# Dx32_V1_0.net
KiCad netlist of a schematic drawn in EAGLE
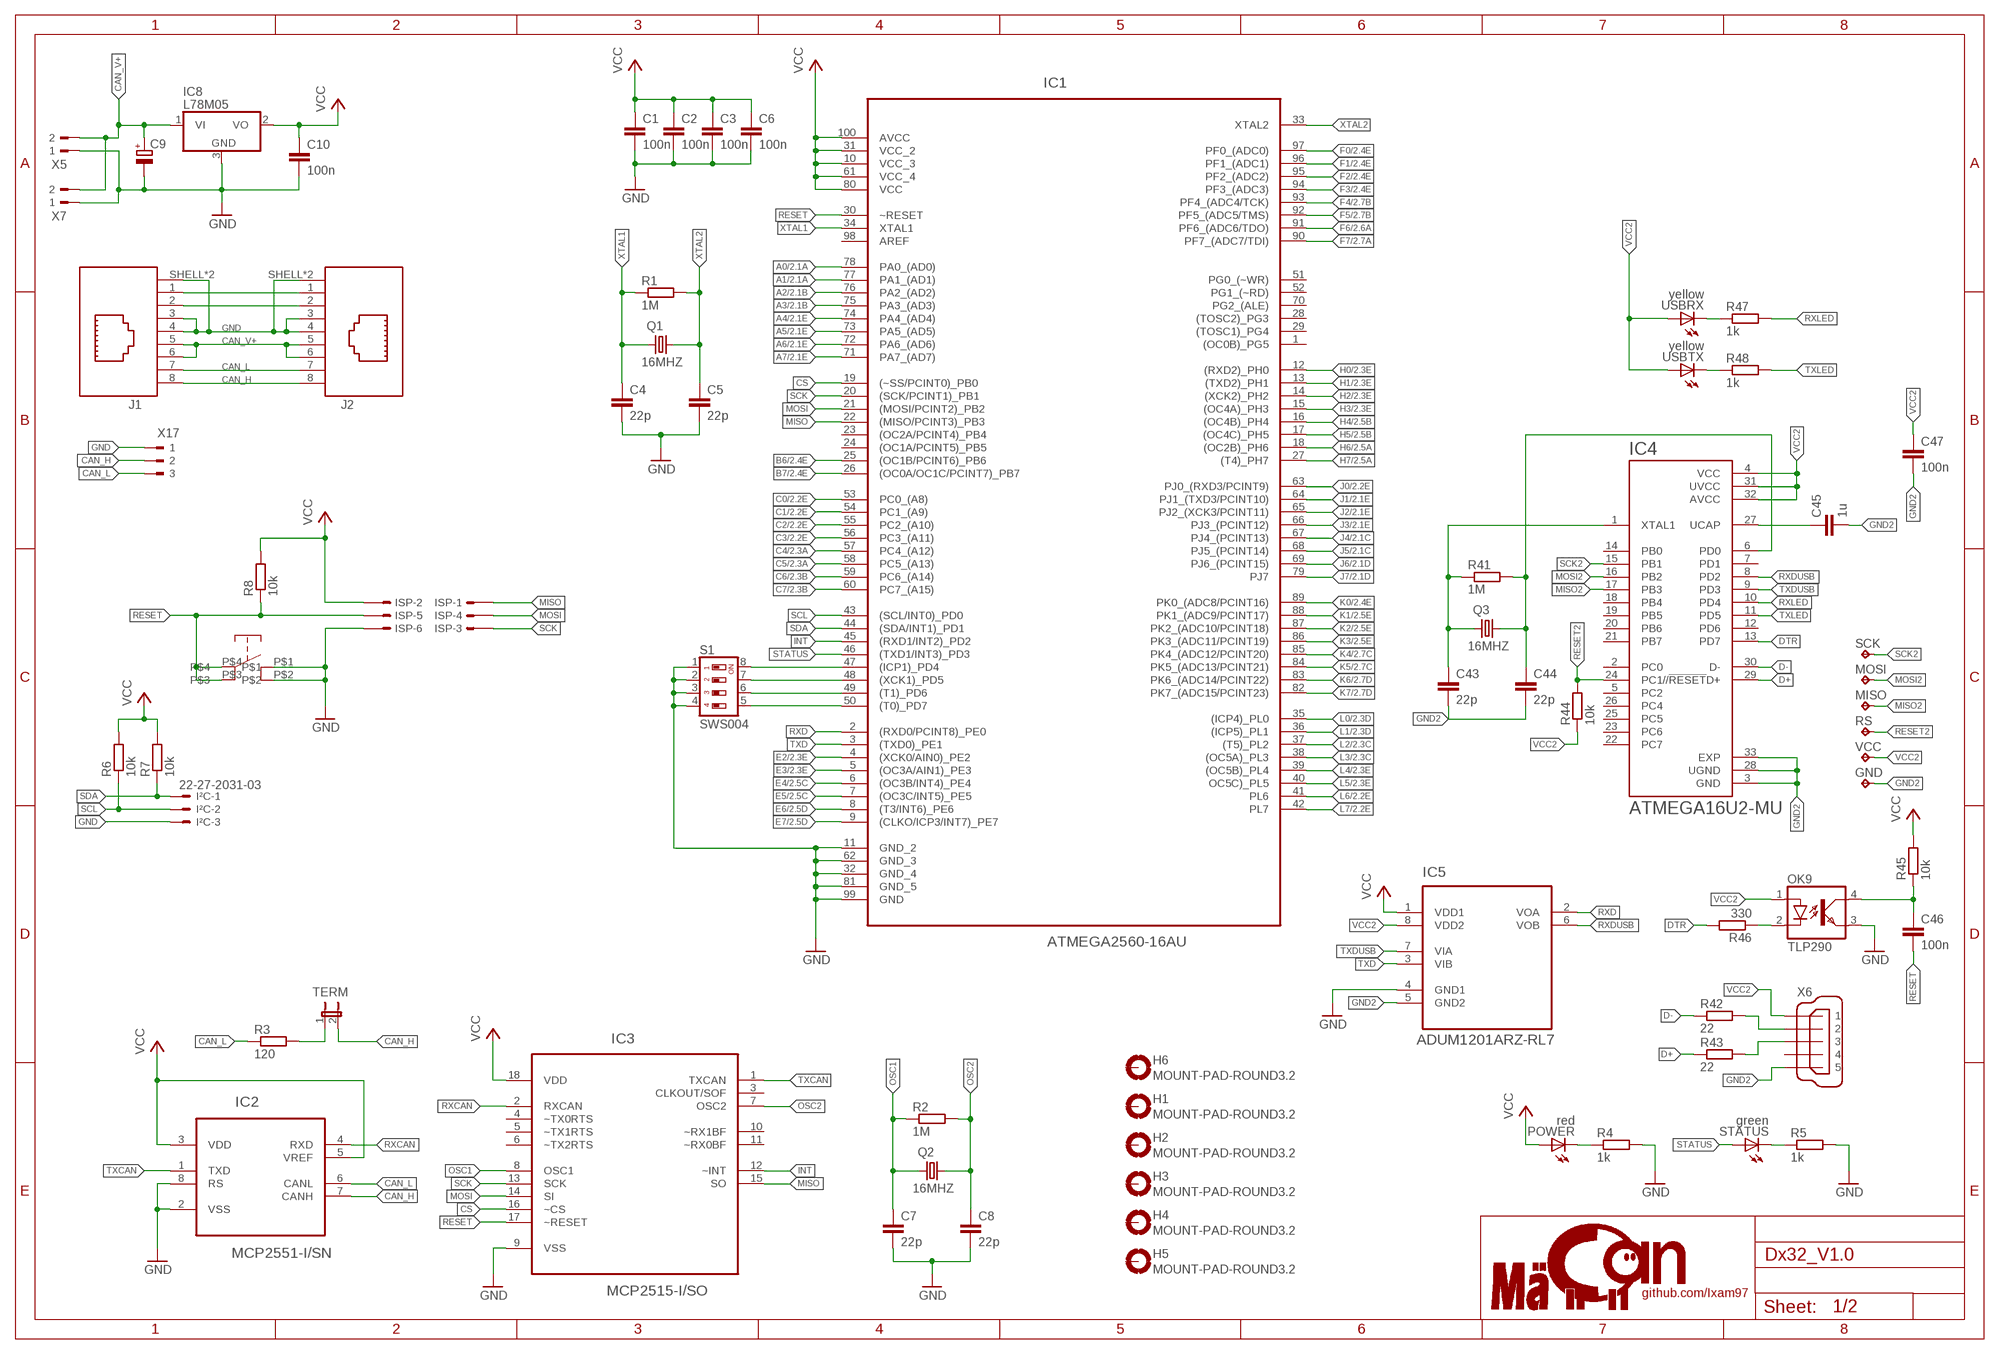
[diagram p0: schematic, sheet 1]
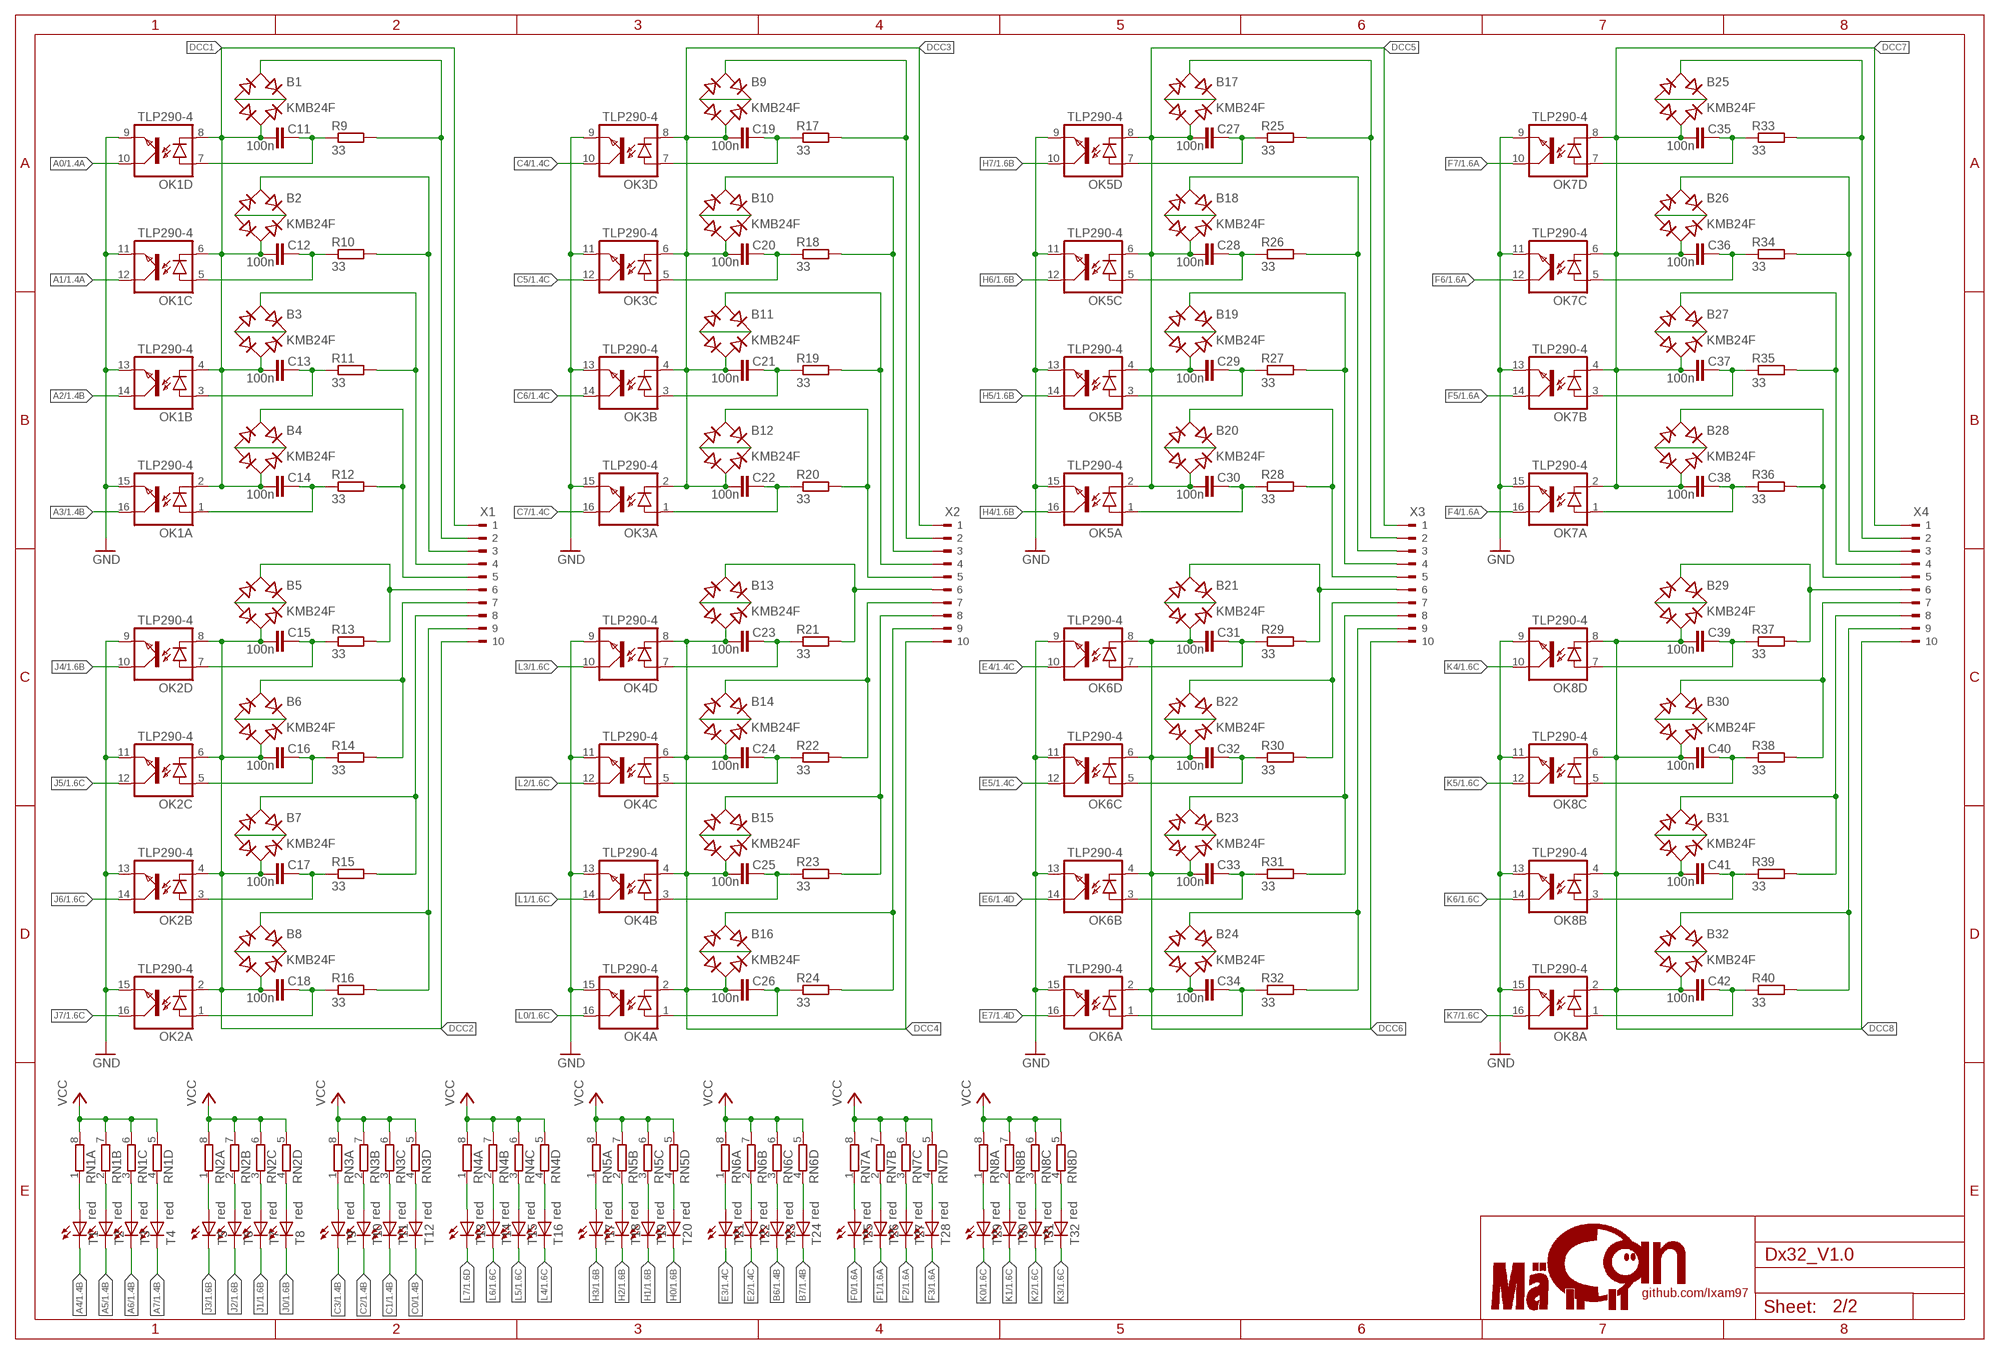
[diagram p1: schematic, sheet 2]

(export (version "E")
  (design (tool "Eeschema 10.0.6"))
  (components
    (comp (ref "C1")
      (value "100n")
      (footprint "eagle-import:C0402")
      (libsource (lib "eagle-import") (part "C-EUC0402"))
    )
    (comp (ref "C2")
      (value "100n")
      (footprint "eagle-import:C0402")
      (libsource (lib "eagle-import") (part "C-EUC0402"))
    )
    (comp (ref "C3")
      (value "100n")
      (footprint "eagle-import:C0402")
      (libsource (lib "eagle-import") (part "C-EUC0402"))
    )
    (comp (ref "C4")
      (value "22p")
      (footprint "eagle-import:C0402")
      (libsource (lib "eagle-import") (part "C-EUC0402"))
    )
    (comp (ref "C5")
      (value "22p")
      (footprint "eagle-import:C0402")
      (libsource (lib "eagle-import") (part "C-EUC0402"))
    )
    (comp (ref "C6")
      (value "100n")
      (footprint "eagle-import:C0402")
      (libsource (lib "eagle-import") (part "C-EUC0402"))
    )
    (comp (ref "C7")
      (value "22p")
      (footprint "eagle-import:C0402")
      (libsource (lib "eagle-import") (part "C-EUC0402"))
    )
    (comp (ref "C8")
      (value "22p")
      (footprint "eagle-import:C0402")
      (libsource (lib "eagle-import") (part "C-EUC0402"))
    )
    (comp (ref "C9")
      (value "CPOL-EUCT3216")
      (footprint "eagle-import:CT3216")
      (libsource (lib "eagle-import") (part "CPOL-EUCT3216"))
    )
    (comp (ref "C10")
      (value "100n")
      (footprint "eagle-import:C0402")
      (libsource (lib "eagle-import") (part "C-EUC0402"))
    )
    (comp (ref "C43")
      (value "22p")
      (footprint "eagle-import:C0402")
      (libsource (lib "eagle-import") (part "C-EUC0402"))
    )
    (comp (ref "C44")
      (value "22p")
      (footprint "eagle-import:C0402")
      (libsource (lib "eagle-import") (part "C-EUC0402"))
    )
    (comp (ref "C45")
      (value "1u")
      (footprint "eagle-import:C0402")
      (libsource (lib "eagle-import") (part "C-EUC0402"))
    )
    (comp (ref "C46")
      (value "100n")
      (footprint "eagle-import:C0402")
      (libsource (lib "eagle-import") (part "C-EUC0402"))
    )
    (comp (ref "C47")
      (value "100n")
      (footprint "eagle-import:C0402")
      (libsource (lib "eagle-import") (part "C-EUC0402"))
    )
    (comp (ref "GND")
      (value "TPB1,27")
      (footprint "eagle-import:B1,27")
      (libsource (lib "eagle-import") (part "TPB1,27"))
    )
    (comp (ref "H1")
      (value "MOUNT-PAD-ROUND3.2")
      (footprint "eagle-import:3,2-PAD")
      (libsource (lib "eagle-import") (part "MOUNT-PAD-ROUND3.2"))
    )
    (comp (ref "H2")
      (value "MOUNT-PAD-ROUND3.2")
      (footprint "eagle-import:3,2-PAD")
      (libsource (lib "eagle-import") (part "MOUNT-PAD-ROUND3.2"))
    )
    (comp (ref "H3")
      (value "MOUNT-PAD-ROUND3.2")
      (footprint "eagle-import:3,2-PAD")
      (libsource (lib "eagle-import") (part "MOUNT-PAD-ROUND3.2"))
    )
    (comp (ref "H4")
      (value "MOUNT-PAD-ROUND3.2")
      (footprint "eagle-import:3,2-PAD")
      (libsource (lib "eagle-import") (part "MOUNT-PAD-ROUND3.2"))
    )
    (comp (ref "H5")
      (value "MOUNT-PAD-ROUND3.2")
      (footprint "eagle-import:3,2-PAD")
      (libsource (lib "eagle-import") (part "MOUNT-PAD-ROUND3.2"))
    )
    (comp (ref "H6")
      (value "MOUNT-PAD-ROUND3.2")
      (footprint "eagle-import:3,2-PAD")
      (libsource (lib "eagle-import") (part "MOUNT-PAD-ROUND3.2"))
    )
    (comp (ref "IC1")
      (value "ATMEGA2560-16AU")
      (footprint "eagle-import:QFP50P1600X1600X120-100N")
      (fields (field (name "MF") "Microchip"))
      (libsource (lib "eagle-import") (part "ATMEGA2560-16AU"))
    )
    (comp (ref "IC2")
      (value "MCP2551-I/SN")
      (footprint "eagle-import:SOIC127P600X175-8N")
      (libsource (lib "eagle-import") (part "MCP2551-I/SN"))
    )
    (comp (ref "IC3")
      (value "MCP2515-I/SO")
      (footprint "eagle-import:SOIC127P1034X264-18N")
      (libsource (lib "eagle-import") (part "MCP2515-I/SO"))
    )
    (comp (ref "IC4")
      (value "ATMEGA16U2-MU")
      (footprint "eagle-import:QFN50P500X500X100-33N")
      (fields (field (name "MF") "Microchip"))
      (libsource (lib "eagle-import") (part "ATMEGA16U2-MU"))
    )
    (comp (ref "IC5")
      (value "ADUM1201ARZ-RL7")
      (footprint "eagle-import:SOIC127P600X175-8N")
      (fields (field (name "MF") "Analog Devices"))
      (libsource (lib "eagle-import") (part "ADUM1201ARZ-RL7"))
    )
    (comp (ref "IC8")
      (value "L78M05")
      (footprint "eagle-import:TO252")
      (fields (field (name "JLCPCB-PART") "C58069"))
      (libsource (lib "eagle-import") (part "78DT05"))
    )
    (comp (ref "ISP")
      (value "057-006-1")
      (footprint "eagle-import:057-006-1")
      (libsource (lib "eagle-import") (part "057-006-1"))
    )
    (comp (ref "I²C")
      (value "22-27-2031-03")
      (footprint "eagle-import:6410-03")
      (fields (field (name "MF") "MOLEX"))
      (libsource (lib "eagle-import") (part "22-?-0327-2031"))
    )
    (comp (ref "J1")
      (value "615008140421")
      (footprint "eagle-import:615008140421")
      (libsource (lib "eagle-import") (part "615008140421"))
    )
    (comp (ref "J2")
      (value "615008140421")
      (footprint "eagle-import:615008140421")
      (libsource (lib "eagle-import") (part "615008140421"))
    )
    (comp (ref "MISO")
      (value "TPB1,27")
      (footprint "eagle-import:B1,27")
      (libsource (lib "eagle-import") (part "TPB1,27"))
    )
    (comp (ref "MOSI")
      (value "TPB1,27")
      (footprint "eagle-import:B1,27")
      (libsource (lib "eagle-import") (part "TPB1,27"))
    )
    (comp (ref "OK9")
      (value "TLP290")
      (footprint "eagle-import:MINI-FLAT-4")
      (libsource (lib "eagle-import") (part "TLP283"))
    )
    (comp (ref "POWER")
      (value "red")
      (footprint "eagle-import:CHIP-LED0805")
      (libsource (lib "eagle-import") (part "LEDCHIP-LED0805"))
    )
    (comp (ref "Q1")
      (value "16MHZ")
      (footprint "eagle-import:3.2X2.5_KX-7")
      (libsource (lib "eagle-import") (part "KX-7"))
    )
    (comp (ref "Q2")
      (value "16MHZ")
      (footprint "eagle-import:3.2X2.5_KX-7")
      (libsource (lib "eagle-import") (part "KX-7"))
    )
    (comp (ref "Q3")
      (value "16MHZ")
      (footprint "eagle-import:3.2X2.5_KX-7")
      (libsource (lib "eagle-import") (part "KX-7"))
    )
    (comp (ref "R1")
      (value "1M")
      (footprint "eagle-import:R0402")
      (libsource (lib "eagle-import") (part "R-EU_R0402"))
    )
    (comp (ref "R2")
      (value "1M")
      (footprint "eagle-import:R0402")
      (libsource (lib "eagle-import") (part "R-EU_R0402"))
    )
    (comp (ref "R3")
      (value "120")
      (footprint "eagle-import:R0402")
      (libsource (lib "eagle-import") (part "R-EU_R0402"))
    )
    (comp (ref "R4")
      (value "1k")
      (footprint "eagle-import:R0402")
      (libsource (lib "eagle-import") (part "R-EU_R0402"))
    )
    (comp (ref "R5")
      (value "1k")
      (footprint "eagle-import:R0402")
      (libsource (lib "eagle-import") (part "R-EU_R0402"))
    )
    (comp (ref "R6")
      (value "10k")
      (footprint "eagle-import:R0402")
      (libsource (lib "eagle-import") (part "R-EU_R0402"))
    )
    (comp (ref "R7")
      (value "10k")
      (footprint "eagle-import:R0402")
      (libsource (lib "eagle-import") (part "R-EU_R0402"))
    )
    (comp (ref "R8")
      (value "10k")
      (footprint "eagle-import:R0402")
      (libsource (lib "eagle-import") (part "R-EU_R0402"))
    )
    (comp (ref "R41")
      (value "1M")
      (footprint "eagle-import:R0402")
      (libsource (lib "eagle-import") (part "R-EU_R0402"))
    )
    (comp (ref "R42")
      (value "22")
      (footprint "eagle-import:R0402")
      (libsource (lib "eagle-import") (part "R-EU_R0402"))
    )
    (comp (ref "R43")
      (value "22")
      (footprint "eagle-import:R0402")
      (libsource (lib "eagle-import") (part "R-EU_R0402"))
    )
    (comp (ref "R44")
      (value "10k")
      (footprint "eagle-import:R0402")
      (libsource (lib "eagle-import") (part "R-EU_R0402"))
    )
    (comp (ref "R45")
      (value "10k")
      (footprint "eagle-import:R0402")
      (libsource (lib "eagle-import") (part "R-EU_R0402"))
    )
    (comp (ref "R46")
      (value "330")
      (footprint "eagle-import:R0402")
      (libsource (lib "eagle-import") (part "R-EU_R0402"))
    )
    (comp (ref "R47")
      (value "1k")
      (footprint "eagle-import:R0402")
      (libsource (lib "eagle-import") (part "R-EU_R0402"))
    )
    (comp (ref "R48")
      (value "1k")
      (footprint "eagle-import:R0402")
      (libsource (lib "eagle-import") (part "R-EU_R0402"))
    )
    (comp (ref "RS")
      (value "TPB1,27")
      (footprint "eagle-import:B1,27")
      (libsource (lib "eagle-import") (part "TPB1,27"))
    )
    (comp (ref "S1")
      (value "SWS004")
      (footprint "eagle-import:SMS-004")
      (libsource (lib "eagle-import") (part "SWS004"))
    )
    (comp (ref "SCK")
      (value "TPB1,27")
      (footprint "eagle-import:B1,27")
      (libsource (lib "eagle-import") (part "TPB1,27"))
    )
    (comp (ref "STATUS")
      (value "green")
      (footprint "eagle-import:CHIP-LED0805")
      (libsource (lib "eagle-import") (part "LEDCHIP-LED0805"))
    )
    (comp (ref "TERM")
      (value "JP1E")
      (footprint "eagle-import:JP1")
      (libsource (lib "eagle-import") (part "JP1E"))
    )
    (comp (ref "U$15")
      (value "BUTTON_JLC")
      (footprint "eagle-import:BUTTON")
      (libsource (lib "eagle-import") (part "BUTTON_JLC"))
    )
    (comp (ref "USBRX")
      (value "yellow")
      (footprint "eagle-import:CHIP-LED0805")
      (libsource (lib "eagle-import") (part "LEDCHIP-LED0805"))
    )
    (comp (ref "USBTX")
      (value "yellow")
      (footprint "eagle-import:CHIP-LED0805")
      (libsource (lib "eagle-import") (part "LEDCHIP-LED0805"))
    )
    (comp (ref "VCC")
      (value "TPB1,27")
      (footprint "eagle-import:B1,27")
      (libsource (lib "eagle-import") (part "TPB1,27"))
    )
    (comp (ref "X5")
      (value "180-2")
      (footprint "eagle-import:180-2")
      (libsource (lib "eagle-import") (part "180-2"))
    )
    (comp (ref "X6")
      (value "MINI-USB_SHIELD5P2-32005-601")
      (footprint "eagle-import:32005-601")
      (libsource (lib "eagle-import") (part "MINI-USB_SHIELD5P2-32005-601"))
    )
    (comp (ref "X7")
      (value "180-2")
      (footprint "eagle-import:180-2")
      (libsource (lib "eagle-import") (part "180-2"))
    )
    (comp (ref "X17")
      (value "180-3")
      (footprint "eagle-import:180-3")
      (libsource (lib "eagle-import") (part "180-3"))
    )
    (comp (ref "B1")
      (value "KMB24F")
      (footprint "eagle-import:MBS")
      (fields (field (name "JLCPCB-PART") "C113927"))
      (libsource (lib "eagle-import") (part "BS2"))
    )
    (comp (ref "B2")
      (value "KMB24F")
      (footprint "eagle-import:MBS")
      (libsource (lib "eagle-import") (part "BS2"))
    )
    (comp (ref "B3")
      (value "KMB24F")
      (footprint "eagle-import:MBS")
      (libsource (lib "eagle-import") (part "BS2"))
    )
    (comp (ref "B4")
      (value "KMB24F")
      (footprint "eagle-import:MBS")
      (libsource (lib "eagle-import") (part "BS2"))
    )
    (comp (ref "B5")
      (value "KMB24F")
      (footprint "eagle-import:MBS")
      (libsource (lib "eagle-import") (part "BS2"))
    )
    (comp (ref "B6")
      (value "KMB24F")
      (footprint "eagle-import:MBS")
      (libsource (lib "eagle-import") (part "BS2"))
    )
    (comp (ref "B7")
      (value "KMB24F")
      (footprint "eagle-import:MBS")
      (libsource (lib "eagle-import") (part "BS2"))
    )
    (comp (ref "B8")
      (value "KMB24F")
      (footprint "eagle-import:MBS")
      (libsource (lib "eagle-import") (part "BS2"))
    )
    (comp (ref "B9")
      (value "KMB24F")
      (footprint "eagle-import:MBS")
      (libsource (lib "eagle-import") (part "BS2"))
    )
    (comp (ref "B10")
      (value "KMB24F")
      (footprint "eagle-import:MBS")
      (libsource (lib "eagle-import") (part "BS2"))
    )
    (comp (ref "B11")
      (value "KMB24F")
      (footprint "eagle-import:MBS")
      (libsource (lib "eagle-import") (part "BS2"))
    )
    (comp (ref "B12")
      (value "KMB24F")
      (footprint "eagle-import:MBS")
      (libsource (lib "eagle-import") (part "BS2"))
    )
    (comp (ref "B13")
      (value "KMB24F")
      (footprint "eagle-import:MBS")
      (libsource (lib "eagle-import") (part "BS2"))
    )
    (comp (ref "B14")
      (value "KMB24F")
      (footprint "eagle-import:MBS")
      (libsource (lib "eagle-import") (part "BS2"))
    )
    (comp (ref "B15")
      (value "KMB24F")
      (footprint "eagle-import:MBS")
      (libsource (lib "eagle-import") (part "BS2"))
    )
    (comp (ref "B16")
      (value "KMB24F")
      (footprint "eagle-import:MBS")
      (libsource (lib "eagle-import") (part "BS2"))
    )
    (comp (ref "B17")
      (value "KMB24F")
      (footprint "eagle-import:MBS")
      (libsource (lib "eagle-import") (part "BS2"))
    )
    (comp (ref "B18")
      (value "KMB24F")
      (footprint "eagle-import:MBS")
      (libsource (lib "eagle-import") (part "BS2"))
    )
    (comp (ref "B19")
      (value "KMB24F")
      (footprint "eagle-import:MBS")
      (libsource (lib "eagle-import") (part "BS2"))
    )
    (comp (ref "B20")
      (value "KMB24F")
      (footprint "eagle-import:MBS")
      (libsource (lib "eagle-import") (part "BS2"))
    )
    (comp (ref "B21")
      (value "KMB24F")
      (footprint "eagle-import:MBS")
      (libsource (lib "eagle-import") (part "BS2"))
    )
    (comp (ref "B22")
      (value "KMB24F")
      (footprint "eagle-import:MBS")
      (libsource (lib "eagle-import") (part "BS2"))
    )
    (comp (ref "B23")
      (value "KMB24F")
      (footprint "eagle-import:MBS")
      (libsource (lib "eagle-import") (part "BS2"))
    )
    (comp (ref "B24")
      (value "KMB24F")
      (footprint "eagle-import:MBS")
      (libsource (lib "eagle-import") (part "BS2"))
    )
    (comp (ref "B25")
      (value "KMB24F")
      (footprint "eagle-import:MBS")
      (libsource (lib "eagle-import") (part "BS2"))
    )
    (comp (ref "B26")
      (value "KMB24F")
      (footprint "eagle-import:MBS")
      (libsource (lib "eagle-import") (part "BS2"))
    )
    (comp (ref "B27")
      (value "KMB24F")
      (footprint "eagle-import:MBS")
      (libsource (lib "eagle-import") (part "BS2"))
    )
    (comp (ref "B28")
      (value "KMB24F")
      (footprint "eagle-import:MBS")
      (libsource (lib "eagle-import") (part "BS2"))
    )
    (comp (ref "B29")
      (value "KMB24F")
      (footprint "eagle-import:MBS")
      (libsource (lib "eagle-import") (part "BS2"))
    )
    (comp (ref "B30")
      (value "KMB24F")
      (footprint "eagle-import:MBS")
      (libsource (lib "eagle-import") (part "BS2"))
    )
    (comp (ref "B31")
      (value "KMB24F")
      (footprint "eagle-import:MBS")
      (libsource (lib "eagle-import") (part "BS2"))
    )
    (comp (ref "B32")
      (value "KMB24F")
      (footprint "eagle-import:MBS")
      (libsource (lib "eagle-import") (part "BS2"))
    )
    (comp (ref "C11")
      (value "100n")
      (footprint "eagle-import:C0402")
      (libsource (lib "eagle-import") (part "C-EUC0402"))
    )
    (comp (ref "C12")
      (value "100n")
      (footprint "eagle-import:C0402")
      (libsource (lib "eagle-import") (part "C-EUC0402"))
    )
    (comp (ref "C13")
      (value "100n")
      (footprint "eagle-import:C0402")
      (libsource (lib "eagle-import") (part "C-EUC0402"))
    )
    (comp (ref "C14")
      (value "100n")
      (footprint "eagle-import:C0402")
      (libsource (lib "eagle-import") (part "C-EUC0402"))
    )
    (comp (ref "C15")
      (value "100n")
      (footprint "eagle-import:C0402")
      (libsource (lib "eagle-import") (part "C-EUC0402"))
    )
    (comp (ref "C16")
      (value "100n")
      (footprint "eagle-import:C0402")
      (libsource (lib "eagle-import") (part "C-EUC0402"))
    )
    (comp (ref "C17")
      (value "100n")
      (footprint "eagle-import:C0402")
      (libsource (lib "eagle-import") (part "C-EUC0402"))
    )
    (comp (ref "C18")
      (value "100n")
      (footprint "eagle-import:C0402")
      (libsource (lib "eagle-import") (part "C-EUC0402"))
    )
    (comp (ref "C19")
      (value "100n")
      (footprint "eagle-import:C0402")
      (libsource (lib "eagle-import") (part "C-EUC0402"))
    )
    (comp (ref "C20")
      (value "100n")
      (footprint "eagle-import:C0402")
      (libsource (lib "eagle-import") (part "C-EUC0402"))
    )
    (comp (ref "C21")
      (value "100n")
      (footprint "eagle-import:C0402")
      (libsource (lib "eagle-import") (part "C-EUC0402"))
    )
    (comp (ref "C22")
      (value "100n")
      (footprint "eagle-import:C0402")
      (libsource (lib "eagle-import") (part "C-EUC0402"))
    )
    (comp (ref "C23")
      (value "100n")
      (footprint "eagle-import:C0402")
      (libsource (lib "eagle-import") (part "C-EUC0402"))
    )
    (comp (ref "C24")
      (value "100n")
      (footprint "eagle-import:C0402")
      (libsource (lib "eagle-import") (part "C-EUC0402"))
    )
    (comp (ref "C25")
      (value "100n")
      (footprint "eagle-import:C0402")
      (libsource (lib "eagle-import") (part "C-EUC0402"))
    )
    (comp (ref "C26")
      (value "100n")
      (footprint "eagle-import:C0402")
      (libsource (lib "eagle-import") (part "C-EUC0402"))
    )
    (comp (ref "C27")
      (value "100n")
      (footprint "eagle-import:C0402")
      (libsource (lib "eagle-import") (part "C-EUC0402"))
    )
    (comp (ref "C28")
      (value "100n")
      (footprint "eagle-import:C0402")
      (libsource (lib "eagle-import") (part "C-EUC0402"))
    )
    (comp (ref "C29")
      (value "100n")
      (footprint "eagle-import:C0402")
      (libsource (lib "eagle-import") (part "C-EUC0402"))
    )
    (comp (ref "C30")
      (value "100n")
      (footprint "eagle-import:C0402")
      (libsource (lib "eagle-import") (part "C-EUC0402"))
    )
    (comp (ref "C31")
      (value "100n")
      (footprint "eagle-import:C0402")
      (libsource (lib "eagle-import") (part "C-EUC0402"))
    )
    (comp (ref "C32")
      (value "100n")
      (footprint "eagle-import:C0402")
      (libsource (lib "eagle-import") (part "C-EUC0402"))
    )
    (comp (ref "C33")
      (value "100n")
      (footprint "eagle-import:C0402")
      (libsource (lib "eagle-import") (part "C-EUC0402"))
    )
    (comp (ref "C34")
      (value "100n")
      (footprint "eagle-import:C0402")
      (libsource (lib "eagle-import") (part "C-EUC0402"))
    )
    (comp (ref "C35")
      (value "100n")
      (footprint "eagle-import:C0402")
      (libsource (lib "eagle-import") (part "C-EUC0402"))
    )
    (comp (ref "C36")
      (value "100n")
      (footprint "eagle-import:C0402")
      (libsource (lib "eagle-import") (part "C-EUC0402"))
    )
    (comp (ref "C37")
      (value "100n")
      (footprint "eagle-import:C0402")
      (libsource (lib "eagle-import") (part "C-EUC0402"))
    )
    (comp (ref "C38")
      (value "100n")
      (footprint "eagle-import:C0402")
      (libsource (lib "eagle-import") (part "C-EUC0402"))
    )
    (comp (ref "C39")
      (value "100n")
      (footprint "eagle-import:C0402")
      (libsource (lib "eagle-import") (part "C-EUC0402"))
    )
    (comp (ref "C40")
      (value "100n")
      (footprint "eagle-import:C0402")
      (libsource (lib "eagle-import") (part "C-EUC0402"))
    )
    (comp (ref "C41")
      (value "100n")
      (footprint "eagle-import:C0402")
      (libsource (lib "eagle-import") (part "C-EUC0402"))
    )
    (comp (ref "C42")
      (value "100n")
      (footprint "eagle-import:C0402")
      (libsource (lib "eagle-import") (part "C-EUC0402"))
    )
    (comp (ref "OK1")
      (value "TLP290-4")
      (footprint "eagle-import:MINI-FLAT-16")
      (fields (field (name "JLCPC-PART") "C39031"))
      (libsource (lib "eagle-import") (part "TLP283-4"))
    )
    (comp (ref "OK2")
      (value "TLP290-4")
      (footprint "eagle-import:MINI-FLAT-16")
      (libsource (lib "eagle-import") (part "TLP283-4"))
    )
    (comp (ref "OK3")
      (value "TLP290-4")
      (footprint "eagle-import:MINI-FLAT-16")
      (libsource (lib "eagle-import") (part "TLP283-4"))
    )
    (comp (ref "OK4")
      (value "TLP290-4")
      (footprint "eagle-import:MINI-FLAT-16")
      (libsource (lib "eagle-import") (part "TLP283-4"))
    )
    (comp (ref "OK5")
      (value "TLP290-4")
      (footprint "eagle-import:MINI-FLAT-16")
      (libsource (lib "eagle-import") (part "TLP283-4"))
    )
    (comp (ref "OK6")
      (value "TLP290-4")
      (footprint "eagle-import:MINI-FLAT-16")
      (libsource (lib "eagle-import") (part "TLP283-4"))
    )
    (comp (ref "OK7")
      (value "TLP290-4")
      (footprint "eagle-import:MINI-FLAT-16")
      (libsource (lib "eagle-import") (part "TLP283-4"))
    )
    (comp (ref "OK8")
      (value "TLP290-4")
      (footprint "eagle-import:MINI-FLAT-16")
      (libsource (lib "eagle-import") (part "TLP283-4"))
    )
    (comp (ref "R9")
      (value "33")
      (footprint "eagle-import:R0402")
      (libsource (lib "eagle-import") (part "R-EU_R0402"))
    )
    (comp (ref "R10")
      (value "33")
      (footprint "eagle-import:R0402")
      (libsource (lib "eagle-import") (part "R-EU_R0402"))
    )
    (comp (ref "R11")
      (value "33")
      (footprint "eagle-import:R0402")
      (libsource (lib "eagle-import") (part "R-EU_R0402"))
    )
    (comp (ref "R12")
      (value "33")
      (footprint "eagle-import:R0402")
      (libsource (lib "eagle-import") (part "R-EU_R0402"))
    )
    (comp (ref "R13")
      (value "33")
      (footprint "eagle-import:R0402")
      (libsource (lib "eagle-import") (part "R-EU_R0402"))
    )
    (comp (ref "R14")
      (value "33")
      (footprint "eagle-import:R0402")
      (libsource (lib "eagle-import") (part "R-EU_R0402"))
    )
    (comp (ref "R15")
      (value "33")
      (footprint "eagle-import:R0402")
      (libsource (lib "eagle-import") (part "R-EU_R0402"))
    )
    (comp (ref "R16")
      (value "33")
      (footprint "eagle-import:R0402")
      (libsource (lib "eagle-import") (part "R-EU_R0402"))
    )
    (comp (ref "R17")
      (value "33")
      (footprint "eagle-import:R0402")
      (libsource (lib "eagle-import") (part "R-EU_R0402"))
    )
    (comp (ref "R18")
      (value "33")
      (footprint "eagle-import:R0402")
      (libsource (lib "eagle-import") (part "R-EU_R0402"))
    )
    (comp (ref "R19")
      (value "33")
      (footprint "eagle-import:R0402")
      (libsource (lib "eagle-import") (part "R-EU_R0402"))
    )
    (comp (ref "R20")
      (value "33")
      (footprint "eagle-import:R0402")
      (libsource (lib "eagle-import") (part "R-EU_R0402"))
    )
    (comp (ref "R21")
      (value "33")
      (footprint "eagle-import:R0402")
      (libsource (lib "eagle-import") (part "R-EU_R0402"))
    )
    (comp (ref "R22")
      (value "33")
      (footprint "eagle-import:R0402")
      (libsource (lib "eagle-import") (part "R-EU_R0402"))
    )
    (comp (ref "R23")
      (value "33")
      (footprint "eagle-import:R0402")
      (libsource (lib "eagle-import") (part "R-EU_R0402"))
    )
    (comp (ref "R24")
      (value "33")
      (footprint "eagle-import:R0402")
      (libsource (lib "eagle-import") (part "R-EU_R0402"))
    )
    (comp (ref "R25")
      (value "33")
      (footprint "eagle-import:R0402")
      (libsource (lib "eagle-import") (part "R-EU_R0402"))
    )
    (comp (ref "R26")
      (value "33")
      (footprint "eagle-import:R0402")
      (libsource (lib "eagle-import") (part "R-EU_R0402"))
    )
    (comp (ref "R27")
      (value "33")
      (footprint "eagle-import:R0402")
      (libsource (lib "eagle-import") (part "R-EU_R0402"))
    )
    (comp (ref "R28")
      (value "33")
      (footprint "eagle-import:R0402")
      (libsource (lib "eagle-import") (part "R-EU_R0402"))
    )
    (comp (ref "R29")
      (value "33")
      (footprint "eagle-import:R0402")
      (libsource (lib "eagle-import") (part "R-EU_R0402"))
    )
    (comp (ref "R30")
      (value "33")
      (footprint "eagle-import:R0402")
      (libsource (lib "eagle-import") (part "R-EU_R0402"))
    )
    (comp (ref "R31")
      (value "33")
      (footprint "eagle-import:R0402")
      (libsource (lib "eagle-import") (part "R-EU_R0402"))
    )
    (comp (ref "R32")
      (value "33")
      (footprint "eagle-import:R0402")
      (libsource (lib "eagle-import") (part "R-EU_R0402"))
    )
    (comp (ref "R33")
      (value "33")
      (footprint "eagle-import:R0402")
      (libsource (lib "eagle-import") (part "R-EU_R0402"))
    )
    (comp (ref "R34")
      (value "33")
      (footprint "eagle-import:R0402")
      (libsource (lib "eagle-import") (part "R-EU_R0402"))
    )
    (comp (ref "R35")
      (value "33")
      (footprint "eagle-import:R0402")
      (libsource (lib "eagle-import") (part "R-EU_R0402"))
    )
    (comp (ref "R36")
      (value "33")
      (footprint "eagle-import:R0402")
      (libsource (lib "eagle-import") (part "R-EU_R0402"))
    )
    (comp (ref "R37")
      (value "33")
      (footprint "eagle-import:R0402")
      (libsource (lib "eagle-import") (part "R-EU_R0402"))
    )
    (comp (ref "R38")
      (value "33")
      (footprint "eagle-import:R0402")
      (libsource (lib "eagle-import") (part "R-EU_R0402"))
    )
    (comp (ref "R39")
      (value "33")
      (footprint "eagle-import:R0402")
      (libsource (lib "eagle-import") (part "R-EU_R0402"))
    )
    (comp (ref "R40")
      (value "33")
      (footprint "eagle-import:R0402")
      (libsource (lib "eagle-import") (part "R-EU_R0402"))
    )
    (comp (ref "RN1")
      (value "4R-N0603-ARV")
      (footprint "eagle-import:0603-ARV")
      (libsource (lib "eagle-import") (part "4R-N0603-ARV"))
    )
    (comp (ref "RN2")
      (value "4R-N0603-ARV")
      (footprint "eagle-import:0603-ARV")
      (libsource (lib "eagle-import") (part "4R-N0603-ARV"))
    )
    (comp (ref "RN3")
      (value "4R-N0603-ARV")
      (footprint "eagle-import:0603-ARV")
      (libsource (lib "eagle-import") (part "4R-N0603-ARV"))
    )
    (comp (ref "RN4")
      (value "4R-N0603-ARV")
      (footprint "eagle-import:0603-ARV")
      (libsource (lib "eagle-import") (part "4R-N0603-ARV"))
    )
    (comp (ref "RN5")
      (value "4R-N0603-ARV")
      (footprint "eagle-import:0603-ARV")
      (libsource (lib "eagle-import") (part "4R-N0603-ARV"))
    )
    (comp (ref "RN6")
      (value "4R-N0603-ARV")
      (footprint "eagle-import:0603-ARV")
      (libsource (lib "eagle-import") (part "4R-N0603-ARV"))
    )
    (comp (ref "RN7")
      (value "4R-N0603-ARV")
      (footprint "eagle-import:0603-ARV")
      (libsource (lib "eagle-import") (part "4R-N0603-ARV"))
    )
    (comp (ref "RN8")
      (value "4R-N0603-ARV")
      (footprint "eagle-import:0603-ARV")
      (libsource (lib "eagle-import") (part "4R-N0603-ARV"))
    )
    (comp (ref "T1")
      (value "red")
      (footprint "eagle-import:CHIP-LED0805")
      (fields (field (name "JLCPCB-PART") "C84256"))
      (libsource (lib "eagle-import") (part "LEDCHIP-LED0805"))
    )
    (comp (ref "T2")
      (value "red")
      (footprint "eagle-import:CHIP-LED0805")
      (libsource (lib "eagle-import") (part "LEDCHIP-LED0805"))
    )
    (comp (ref "T3")
      (value "red")
      (footprint "eagle-import:CHIP-LED0805")
      (libsource (lib "eagle-import") (part "LEDCHIP-LED0805"))
    )
    (comp (ref "T4")
      (value "red")
      (footprint "eagle-import:CHIP-LED0805")
      (libsource (lib "eagle-import") (part "LEDCHIP-LED0805"))
    )
    (comp (ref "T5")
      (value "red")
      (footprint "eagle-import:CHIP-LED0805")
      (libsource (lib "eagle-import") (part "LEDCHIP-LED0805"))
    )
    (comp (ref "T6")
      (value "red")
      (footprint "eagle-import:CHIP-LED0805")
      (libsource (lib "eagle-import") (part "LEDCHIP-LED0805"))
    )
    (comp (ref "T7")
      (value "red")
      (footprint "eagle-import:CHIP-LED0805")
      (libsource (lib "eagle-import") (part "LEDCHIP-LED0805"))
    )
    (comp (ref "T8")
      (value "red")
      (footprint "eagle-import:CHIP-LED0805")
      (libsource (lib "eagle-import") (part "LEDCHIP-LED0805"))
    )
    (comp (ref "T9")
      (value "red")
      (footprint "eagle-import:CHIP-LED0805")
      (libsource (lib "eagle-import") (part "LEDCHIP-LED0805"))
    )
    (comp (ref "T10")
      (value "red")
      (footprint "eagle-import:CHIP-LED0805")
      (libsource (lib "eagle-import") (part "LEDCHIP-LED0805"))
    )
    (comp (ref "T11")
      (value "red")
      (footprint "eagle-import:CHIP-LED0805")
      (libsource (lib "eagle-import") (part "LEDCHIP-LED0805"))
    )
    (comp (ref "T12")
      (value "red")
      (footprint "eagle-import:CHIP-LED0805")
      (libsource (lib "eagle-import") (part "LEDCHIP-LED0805"))
    )
    (comp (ref "T13")
      (value "red")
      (footprint "eagle-import:CHIP-LED0805")
      (libsource (lib "eagle-import") (part "LEDCHIP-LED0805"))
    )
    (comp (ref "T14")
      (value "red")
      (footprint "eagle-import:CHIP-LED0805")
      (libsource (lib "eagle-import") (part "LEDCHIP-LED0805"))
    )
    (comp (ref "T15")
      (value "red")
      (footprint "eagle-import:CHIP-LED0805")
      (libsource (lib "eagle-import") (part "LEDCHIP-LED0805"))
    )
    (comp (ref "T16")
      (value "red")
      (footprint "eagle-import:CHIP-LED0805")
      (libsource (lib "eagle-import") (part "LEDCHIP-LED0805"))
    )
    (comp (ref "T17")
      (value "red")
      (footprint "eagle-import:CHIP-LED0805")
      (libsource (lib "eagle-import") (part "LEDCHIP-LED0805"))
    )
    (comp (ref "T18")
      (value "red")
      (footprint "eagle-import:CHIP-LED0805")
      (libsource (lib "eagle-import") (part "LEDCHIP-LED0805"))
    )
    (comp (ref "T19")
      (value "red")
      (footprint "eagle-import:CHIP-LED0805")
      (libsource (lib "eagle-import") (part "LEDCHIP-LED0805"))
    )
    (comp (ref "T20")
      (value "red")
      (footprint "eagle-import:CHIP-LED0805")
      (libsource (lib "eagle-import") (part "LEDCHIP-LED0805"))
    )
    (comp (ref "T21")
      (value "red")
      (footprint "eagle-import:CHIP-LED0805")
      (libsource (lib "eagle-import") (part "LEDCHIP-LED0805"))
    )
    (comp (ref "T22")
      (value "red")
      (footprint "eagle-import:CHIP-LED0805")
      (libsource (lib "eagle-import") (part "LEDCHIP-LED0805"))
    )
    (comp (ref "T23")
      (value "red")
      (footprint "eagle-import:CHIP-LED0805")
      (libsource (lib "eagle-import") (part "LEDCHIP-LED0805"))
    )
    (comp (ref "T24")
      (value "red")
      (footprint "eagle-import:CHIP-LED0805")
      (libsource (lib "eagle-import") (part "LEDCHIP-LED0805"))
    )
    (comp (ref "T25")
      (value "red")
      (footprint "eagle-import:CHIP-LED0805")
      (libsource (lib "eagle-import") (part "LEDCHIP-LED0805"))
    )
    (comp (ref "T26")
      (value "red")
      (footprint "eagle-import:CHIP-LED0805")
      (libsource (lib "eagle-import") (part "LEDCHIP-LED0805"))
    )
    (comp (ref "T27")
      (value "red")
      (footprint "eagle-import:CHIP-LED0805")
      (libsource (lib "eagle-import") (part "LEDCHIP-LED0805"))
    )
    (comp (ref "T28")
      (value "red")
      (footprint "eagle-import:CHIP-LED0805")
      (libsource (lib "eagle-import") (part "LEDCHIP-LED0805"))
    )
    (comp (ref "T29")
      (value "red")
      (footprint "eagle-import:CHIP-LED0805")
      (libsource (lib "eagle-import") (part "LEDCHIP-LED0805"))
    )
    (comp (ref "T30")
      (value "red")
      (footprint "eagle-import:CHIP-LED0805")
      (libsource (lib "eagle-import") (part "LEDCHIP-LED0805"))
    )
    (comp (ref "T31")
      (value "red")
      (footprint "eagle-import:CHIP-LED0805")
      (libsource (lib "eagle-import") (part "LEDCHIP-LED0805"))
    )
    (comp (ref "T32")
      (value "red")
      (footprint "eagle-import:CHIP-LED0805")
      (libsource (lib "eagle-import") (part "LEDCHIP-LED0805"))
    )
    (comp (ref "X1")
      (value "180-10")
      (footprint "eagle-import:180-10")
      (libsource (lib "eagle-import") (part "180-10"))
    )
    (comp (ref "X2")
      (value "180-10")
      (footprint "eagle-import:180-10")
      (libsource (lib "eagle-import") (part "180-10"))
    )
    (comp (ref "X3")
      (value "180-10")
      (footprint "eagle-import:180-10")
      (libsource (lib "eagle-import") (part "180-10"))
    )
    (comp (ref "X4")
      (value "180-10")
      (footprint "eagle-import:180-10")
      (libsource (lib "eagle-import") (part "180-10"))
    )
  )
  (nets
    (net (code "1") (name "A0") (class "Default")
      (node (ref "IC1") (pin "78") (pinfunction "PA0_(AD0)_78") (pintype "bidirectional"))
      (node (ref "OK1") (pin "10") (pinfunction "COL_10") (pintype "passive"))
    )
    (net (code "2") (name "A1") (class "Default")
      (node (ref "IC1") (pin "77") (pinfunction "PA1_(AD1)_77") (pintype "bidirectional"))
      (node (ref "OK1") (pin "12") (pinfunction "COL_12") (pintype "passive"))
    )
    (net (code "3") (name "A2") (class "Default")
      (node (ref "IC1") (pin "76") (pinfunction "PA2_(AD2)_76") (pintype "bidirectional"))
      (node (ref "OK1") (pin "14") (pinfunction "COL_14") (pintype "passive"))
    )
    (net (code "4") (name "A3") (class "Default")
      (node (ref "IC1") (pin "75") (pinfunction "PA3_(AD3)_75") (pintype "bidirectional"))
      (node (ref "OK1") (pin "16") (pinfunction "COL_16") (pintype "passive"))
    )
    (net (code "5") (name "A4") (class "Default")
      (node (ref "IC1") (pin "74") (pinfunction "PA4_(AD4)_74") (pintype "bidirectional"))
      (node (ref "T1") (pin "C") (pinfunction "C_C") (pintype "passive"))
    )
    (net (code "6") (name "A5") (class "Default")
      (node (ref "IC1") (pin "73") (pinfunction "PA5_(AD5)_73") (pintype "bidirectional"))
      (node (ref "T2") (pin "C") (pinfunction "C_C") (pintype "passive"))
    )
    (net (code "7") (name "A6") (class "Default")
      (node (ref "IC1") (pin "72") (pinfunction "PA6_(AD6)_72") (pintype "bidirectional"))
      (node (ref "T3") (pin "C") (pinfunction "C_C") (pintype "passive"))
    )
    (net (code "8") (name "A7") (class "Default")
      (node (ref "IC1") (pin "71") (pinfunction "PA7_(AD7)_71") (pintype "bidirectional"))
      (node (ref "T4") (pin "C") (pinfunction "C_C") (pintype "passive"))
    )
    (net (code "9") (name "B6") (class "Default")
      (node (ref "IC1") (pin "25") (pinfunction "(OC1B/PCINT6)_PB6_25") (pintype "bidirectional"))
      (node (ref "T23") (pin "C") (pinfunction "C_C") (pintype "passive"))
    )
    (net (code "10") (name "B7") (class "Default")
      (node (ref "IC1") (pin "26") (pinfunction "(OC0A/OC1C/PCINT7)_PB7_26") (pintype "bidirectional"))
      (node (ref "T24") (pin "C") (pinfunction "C_C") (pintype "passive"))
    )
    (net (code "11") (name "C0") (class "Default")
      (node (ref "IC1") (pin "53") (pinfunction "PC0_(A8)_53") (pintype "bidirectional"))
      (node (ref "T12") (pin "C") (pinfunction "C_C") (pintype "passive"))
    )
    (net (code "12") (name "C1") (class "Default")
      (node (ref "IC1") (pin "54") (pinfunction "PC1_(A9)_54") (pintype "bidirectional"))
      (node (ref "T11") (pin "C") (pinfunction "C_C") (pintype "passive"))
    )
    (net (code "13") (name "C2") (class "Default")
      (node (ref "IC1") (pin "55") (pinfunction "PC2_(A10)_55") (pintype "bidirectional"))
      (node (ref "T10") (pin "C") (pinfunction "C_C") (pintype "passive"))
    )
    (net (code "14") (name "C3") (class "Default")
      (node (ref "IC1") (pin "56") (pinfunction "PC3_(A11)_56") (pintype "bidirectional"))
      (node (ref "T9") (pin "C") (pinfunction "C_C") (pintype "passive"))
    )
    (net (code "15") (name "C4") (class "Default")
      (node (ref "IC1") (pin "57") (pinfunction "PC4_(A12)_57") (pintype "bidirectional"))
      (node (ref "OK3") (pin "10") (pinfunction "COL_10") (pintype "passive"))
    )
    (net (code "16") (name "C5") (class "Default")
      (node (ref "IC1") (pin "58") (pinfunction "PC5_(A13)_58") (pintype "bidirectional"))
      (node (ref "OK3") (pin "12") (pinfunction "COL_12") (pintype "passive"))
    )
    (net (code "17") (name "C6") (class "Default")
      (node (ref "IC1") (pin "59") (pinfunction "PC6_(A14)_59") (pintype "bidirectional"))
      (node (ref "OK3") (pin "14") (pinfunction "COL_14") (pintype "passive"))
    )
    (net (code "18") (name "C7") (class "Default")
      (node (ref "IC1") (pin "60") (pinfunction "PC7_(A15)_60") (pintype "bidirectional"))
      (node (ref "OK3") (pin "16") (pinfunction "COL_16") (pintype "passive"))
    )
    (net (code "19") (name "CAN_H") (class "Default")
      (node (ref "IC2") (pin "7") (pinfunction "CANH_7") (pintype "bidirectional"))
      (node (ref "J1") (pin "8") (pinfunction "8_8") (pintype "passive"))
      (node (ref "J2") (pin "8") (pinfunction "8_8") (pintype "passive"))
      (node (ref "TERM") (pin "2") (pinfunction "2_2") (pintype "passive"))
      (node (ref "X17") (pin "2") (pinfunction "2_2") (pintype "passive"))
    )
    (net (code "20") (name "CAN_L") (class "Default")
      (node (ref "IC2") (pin "6") (pinfunction "CANL_6") (pintype "bidirectional"))
      (node (ref "J1") (pin "7") (pinfunction "7_7") (pintype "passive"))
      (node (ref "J2") (pin "7") (pinfunction "7_7") (pintype "passive"))
      (node (ref "R3") (pin "1") (pinfunction "1_1") (pintype "passive"))
      (node (ref "X17") (pin "3") (pinfunction "3_3") (pintype "passive"))
    )
    (net (code "21") (name "CAN_V+") (class "Default")
      (node (ref "C9") (pin "+") (pinfunction "+_+") (pintype "passive"))
      (node (ref "IC8") (pin "1") (pinfunction "VI_1") (pintype "input"))
      (node (ref "J1") (pin "5") (pinfunction "5_5") (pintype "passive"))
      (node (ref "J1") (pin "6") (pinfunction "6_6") (pintype "passive"))
      (node (ref "J2") (pin "5") (pinfunction "5_5") (pintype "passive"))
      (node (ref "J2") (pin "6") (pinfunction "6_6") (pintype "passive"))
      (node (ref "X5") (pin "2") (pinfunction "2_2") (pintype "passive"))
      (node (ref "X7") (pin "2") (pinfunction "2_2") (pintype "passive"))
    )
    (net (code "22") (name "CS") (class "Default")
      (node (ref "IC1") (pin "19") (pinfunction "(~{SS/PCINT0})_PB0_19") (pintype "bidirectional"))
      (node (ref "IC3") (pin "16") (pinfunction "~{CS}_16") (pintype "input"))
    )
    (net (code "23") (name "D+") (class "Default")
      (node (ref "IC4") (pin "29") (pinfunction "D+_29") (pintype "bidirectional"))
      (node (ref "R43") (pin "1") (pinfunction "1_1") (pintype "passive"))
    )
    (net (code "24") (name "D-") (class "Default")
      (node (ref "IC4") (pin "30") (pinfunction "D-_30") (pintype "bidirectional"))
      (node (ref "R42") (pin "1") (pinfunction "1_1") (pintype "passive"))
    )
    (net (code "25") (name "DCC1") (class "Default")
      (node (ref "B1") (pin "AC2") (pinfunction "AC2_AC2") (pintype "passive"))
      (node (ref "B2") (pin "AC2") (pinfunction "AC2_AC2") (pintype "passive"))
      (node (ref "B3") (pin "AC2") (pinfunction "AC2_AC2") (pintype "passive"))
      (node (ref "B4") (pin "AC2") (pinfunction "AC2_AC2") (pintype "passive"))
      (node (ref "C11") (pin "2") (pinfunction "2_2") (pintype "passive"))
      (node (ref "C12") (pin "2") (pinfunction "2_2") (pintype "passive"))
      (node (ref "C13") (pin "2") (pinfunction "2_2") (pintype "passive"))
      (node (ref "C14") (pin "2") (pinfunction "2_2") (pintype "passive"))
      (node (ref "OK1") (pin "2") (pinfunction "C_2") (pintype "passive"))
      (node (ref "OK1") (pin "4") (pinfunction "C_4") (pintype "passive"))
      (node (ref "OK1") (pin "6") (pinfunction "C_6") (pintype "passive"))
      (node (ref "OK1") (pin "8") (pinfunction "C_8") (pintype "passive"))
      (node (ref "X1") (pin "1") (pinfunction "1_1") (pintype "passive"))
    )
    (net (code "26") (name "DCC2") (class "Default")
      (node (ref "B5") (pin "AC2") (pinfunction "AC2_AC2") (pintype "passive"))
      (node (ref "B6") (pin "AC2") (pinfunction "AC2_AC2") (pintype "passive"))
      (node (ref "B7") (pin "AC2") (pinfunction "AC2_AC2") (pintype "passive"))
      (node (ref "B8") (pin "AC2") (pinfunction "AC2_AC2") (pintype "passive"))
      (node (ref "C15") (pin "2") (pinfunction "2_2") (pintype "passive"))
      (node (ref "C16") (pin "2") (pinfunction "2_2") (pintype "passive"))
      (node (ref "C17") (pin "2") (pinfunction "2_2") (pintype "passive"))
      (node (ref "C18") (pin "2") (pinfunction "2_2") (pintype "passive"))
      (node (ref "OK2") (pin "2") (pinfunction "C_2") (pintype "passive"))
      (node (ref "OK2") (pin "4") (pinfunction "C_4") (pintype "passive"))
      (node (ref "OK2") (pin "6") (pinfunction "C_6") (pintype "passive"))
      (node (ref "OK2") (pin "8") (pinfunction "C_8") (pintype "passive"))
      (node (ref "X1") (pin "10") (pinfunction "10_10") (pintype "passive"))
    )
    (net (code "27") (name "DCC3") (class "Default")
      (node (ref "B10") (pin "AC2") (pinfunction "AC2_AC2") (pintype "passive"))
      (node (ref "B11") (pin "AC2") (pinfunction "AC2_AC2") (pintype "passive"))
      (node (ref "B12") (pin "AC2") (pinfunction "AC2_AC2") (pintype "passive"))
      (node (ref "B9") (pin "AC2") (pinfunction "AC2_AC2") (pintype "passive"))
      (node (ref "C19") (pin "2") (pinfunction "2_2") (pintype "passive"))
      (node (ref "C20") (pin "2") (pinfunction "2_2") (pintype "passive"))
      (node (ref "C21") (pin "2") (pinfunction "2_2") (pintype "passive"))
      (node (ref "C22") (pin "2") (pinfunction "2_2") (pintype "passive"))
      (node (ref "OK3") (pin "2") (pinfunction "C_2") (pintype "passive"))
      (node (ref "OK3") (pin "4") (pinfunction "C_4") (pintype "passive"))
      (node (ref "OK3") (pin "6") (pinfunction "C_6") (pintype "passive"))
      (node (ref "OK3") (pin "8") (pinfunction "C_8") (pintype "passive"))
      (node (ref "X2") (pin "1") (pinfunction "1_1") (pintype "passive"))
    )
    (net (code "28") (name "DCC4") (class "Default")
      (node (ref "B13") (pin "AC2") (pinfunction "AC2_AC2") (pintype "passive"))
      (node (ref "B14") (pin "AC2") (pinfunction "AC2_AC2") (pintype "passive"))
      (node (ref "B15") (pin "AC2") (pinfunction "AC2_AC2") (pintype "passive"))
      (node (ref "B16") (pin "AC2") (pinfunction "AC2_AC2") (pintype "passive"))
      (node (ref "C23") (pin "2") (pinfunction "2_2") (pintype "passive"))
      (node (ref "C24") (pin "2") (pinfunction "2_2") (pintype "passive"))
      (node (ref "C25") (pin "2") (pinfunction "2_2") (pintype "passive"))
      (node (ref "C26") (pin "2") (pinfunction "2_2") (pintype "passive"))
      (node (ref "OK4") (pin "2") (pinfunction "C_2") (pintype "passive"))
      (node (ref "OK4") (pin "4") (pinfunction "C_4") (pintype "passive"))
      (node (ref "OK4") (pin "6") (pinfunction "C_6") (pintype "passive"))
      (node (ref "OK4") (pin "8") (pinfunction "C_8") (pintype "passive"))
      (node (ref "X2") (pin "10") (pinfunction "10_10") (pintype "passive"))
    )
    (net (code "29") (name "DCC5") (class "Default")
      (node (ref "B17") (pin "AC2") (pinfunction "AC2_AC2") (pintype "passive"))
      (node (ref "B18") (pin "AC2") (pinfunction "AC2_AC2") (pintype "passive"))
      (node (ref "B19") (pin "AC2") (pinfunction "AC2_AC2") (pintype "passive"))
      (node (ref "B20") (pin "AC2") (pinfunction "AC2_AC2") (pintype "passive"))
      (node (ref "C27") (pin "2") (pinfunction "2_2") (pintype "passive"))
      (node (ref "C28") (pin "2") (pinfunction "2_2") (pintype "passive"))
      (node (ref "C29") (pin "2") (pinfunction "2_2") (pintype "passive"))
      (node (ref "C30") (pin "2") (pinfunction "2_2") (pintype "passive"))
      (node (ref "OK5") (pin "2") (pinfunction "C_2") (pintype "passive"))
      (node (ref "OK5") (pin "4") (pinfunction "C_4") (pintype "passive"))
      (node (ref "OK5") (pin "6") (pinfunction "C_6") (pintype "passive"))
      (node (ref "OK5") (pin "8") (pinfunction "C_8") (pintype "passive"))
      (node (ref "X3") (pin "1") (pinfunction "1_1") (pintype "passive"))
    )
    (net (code "30") (name "DCC6") (class "Default")
      (node (ref "B21") (pin "AC2") (pinfunction "AC2_AC2") (pintype "passive"))
      (node (ref "B22") (pin "AC2") (pinfunction "AC2_AC2") (pintype "passive"))
      (node (ref "B23") (pin "AC2") (pinfunction "AC2_AC2") (pintype "passive"))
      (node (ref "B24") (pin "AC2") (pinfunction "AC2_AC2") (pintype "passive"))
      (node (ref "C31") (pin "2") (pinfunction "2_2") (pintype "passive"))
      (node (ref "C32") (pin "2") (pinfunction "2_2") (pintype "passive"))
      (node (ref "C33") (pin "2") (pinfunction "2_2") (pintype "passive"))
      (node (ref "C34") (pin "2") (pinfunction "2_2") (pintype "passive"))
      (node (ref "OK6") (pin "2") (pinfunction "C_2") (pintype "passive"))
      (node (ref "OK6") (pin "4") (pinfunction "C_4") (pintype "passive"))
      (node (ref "OK6") (pin "6") (pinfunction "C_6") (pintype "passive"))
      (node (ref "OK6") (pin "8") (pinfunction "C_8") (pintype "passive"))
      (node (ref "X3") (pin "10") (pinfunction "10_10") (pintype "passive"))
    )
    (net (code "31") (name "DCC7") (class "Default")
      (node (ref "B25") (pin "AC2") (pinfunction "AC2_AC2") (pintype "passive"))
      (node (ref "B26") (pin "AC2") (pinfunction "AC2_AC2") (pintype "passive"))
      (node (ref "B27") (pin "AC2") (pinfunction "AC2_AC2") (pintype "passive"))
      (node (ref "B28") (pin "AC2") (pinfunction "AC2_AC2") (pintype "passive"))
      (node (ref "C35") (pin "2") (pinfunction "2_2") (pintype "passive"))
      (node (ref "C36") (pin "2") (pinfunction "2_2") (pintype "passive"))
      (node (ref "C37") (pin "2") (pinfunction "2_2") (pintype "passive"))
      (node (ref "C38") (pin "2") (pinfunction "2_2") (pintype "passive"))
      (node (ref "OK7") (pin "2") (pinfunction "C_2") (pintype "passive"))
      (node (ref "OK7") (pin "4") (pinfunction "C_4") (pintype "passive"))
      (node (ref "OK7") (pin "6") (pinfunction "C_6") (pintype "passive"))
      (node (ref "OK7") (pin "8") (pinfunction "C_8") (pintype "passive"))
      (node (ref "X4") (pin "1") (pinfunction "1_1") (pintype "passive"))
    )
    (net (code "32") (name "DCC8") (class "Default")
      (node (ref "B29") (pin "AC2") (pinfunction "AC2_AC2") (pintype "passive"))
      (node (ref "B30") (pin "AC2") (pinfunction "AC2_AC2") (pintype "passive"))
      (node (ref "B31") (pin "AC2") (pinfunction "AC2_AC2") (pintype "passive"))
      (node (ref "B32") (pin "AC2") (pinfunction "AC2_AC2") (pintype "passive"))
      (node (ref "C39") (pin "2") (pinfunction "2_2") (pintype "passive"))
      (node (ref "C40") (pin "2") (pinfunction "2_2") (pintype "passive"))
      (node (ref "C41") (pin "2") (pinfunction "2_2") (pintype "passive"))
      (node (ref "C42") (pin "2") (pinfunction "2_2") (pintype "passive"))
      (node (ref "OK8") (pin "2") (pinfunction "C_2") (pintype "passive"))
      (node (ref "OK8") (pin "4") (pinfunction "C_4") (pintype "passive"))
      (node (ref "OK8") (pin "6") (pinfunction "C_6") (pintype "passive"))
      (node (ref "OK8") (pin "8") (pinfunction "C_8") (pintype "passive"))
      (node (ref "X4") (pin "10") (pinfunction "10_10") (pintype "passive"))
    )
    (net (code "33") (name "DTR") (class "Default")
      (node (ref "IC4") (pin "13") (pinfunction "PD7_13") (pintype "bidirectional"))
      (node (ref "R46") (pin "2") (pinfunction "2_2") (pintype "passive"))
    )
    (net (code "34") (name "E2") (class "Default")
      (node (ref "IC1") (pin "4") (pinfunction "(XCK0/AIN0)_PE2_4") (pintype "bidirectional"))
      (node (ref "T22") (pin "C") (pinfunction "C_C") (pintype "passive"))
    )
    (net (code "35") (name "E3") (class "Default")
      (node (ref "IC1") (pin "5") (pinfunction "(OC3A/AIN1)_PE3_5") (pintype "bidirectional"))
      (node (ref "T21") (pin "C") (pinfunction "C_C") (pintype "passive"))
    )
    (net (code "36") (name "E4") (class "Default")
      (node (ref "IC1") (pin "6") (pinfunction "(OC3B/INT4)_PE4_6") (pintype "bidirectional"))
      (node (ref "OK6") (pin "10") (pinfunction "COL_10") (pintype "passive"))
    )
    (net (code "37") (name "E5") (class "Default")
      (node (ref "IC1") (pin "7") (pinfunction "(OC3C/INT5)_PE5_7") (pintype "bidirectional"))
      (node (ref "OK6") (pin "12") (pinfunction "COL_12") (pintype "passive"))
    )
    (net (code "38") (name "E6") (class "Default")
      (node (ref "IC1") (pin "8") (pinfunction "(T3/INT6)_PE6_8") (pintype "bidirectional"))
      (node (ref "OK6") (pin "14") (pinfunction "COL_14") (pintype "passive"))
    )
    (net (code "39") (name "E7") (class "Default")
      (node (ref "IC1") (pin "9") (pinfunction "(CLKO/ICP3/INT7)_PE7_9") (pintype "bidirectional"))
      (node (ref "OK6") (pin "16") (pinfunction "COL_16") (pintype "passive"))
    )
    (net (code "40") (name "F0") (class "Default")
      (node (ref "IC1") (pin "97") (pinfunction "PF0_(ADC0)_97") (pintype "bidirectional"))
      (node (ref "T25") (pin "C") (pinfunction "C_C") (pintype "passive"))
    )
    (net (code "41") (name "F1") (class "Default")
      (node (ref "IC1") (pin "96") (pinfunction "PF1_(ADC1)_96") (pintype "bidirectional"))
      (node (ref "T26") (pin "C") (pinfunction "C_C") (pintype "passive"))
    )
    (net (code "42") (name "F2") (class "Default")
      (node (ref "IC1") (pin "95") (pinfunction "PF2_(ADC2)_95") (pintype "bidirectional"))
      (node (ref "T27") (pin "C") (pinfunction "C_C") (pintype "passive"))
    )
    (net (code "43") (name "F3") (class "Default")
      (node (ref "IC1") (pin "94") (pinfunction "PF3_(ADC3)_94") (pintype "bidirectional"))
      (node (ref "T28") (pin "C") (pinfunction "C_C") (pintype "passive"))
    )
    (net (code "44") (name "F4") (class "Default")
      (node (ref "IC1") (pin "93") (pinfunction "PF4_(ADC4/TCK)_93") (pintype "bidirectional"))
      (node (ref "OK7") (pin "16") (pinfunction "COL_16") (pintype "passive"))
    )
    (net (code "45") (name "F5") (class "Default")
      (node (ref "IC1") (pin "92") (pinfunction "PF5_(ADC5/TMS)_92") (pintype "bidirectional"))
      (node (ref "OK7") (pin "14") (pinfunction "COL_14") (pintype "passive"))
    )
    (net (code "46") (name "F6") (class "Default")
      (node (ref "IC1") (pin "91") (pinfunction "PF6_(ADC6/TDO)_91") (pintype "bidirectional"))
      (node (ref "OK7") (pin "12") (pinfunction "COL_12") (pintype "passive"))
    )
    (net (code "47") (name "F7") (class "Default")
      (node (ref "IC1") (pin "90") (pinfunction "PF7_(ADC7/TDI)_90") (pintype "bidirectional"))
      (node (ref "OK7") (pin "10") (pinfunction "COL_10") (pintype "passive"))
    )
    (net (code "48") (name "GND") (class "Default")
      (node (ref "C1") (pin "2") (pinfunction "2_2") (pintype "passive"))
      (node (ref "C10") (pin "2") (pinfunction "2_2") (pintype "passive"))
      (node (ref "C2") (pin "2") (pinfunction "2_2") (pintype "passive"))
      (node (ref "C3") (pin "2") (pinfunction "2_2") (pintype "passive"))
      (node (ref "C4") (pin "2") (pinfunction "2_2") (pintype "passive"))
      (node (ref "C5") (pin "2") (pinfunction "2_2") (pintype "passive"))
      (node (ref "C6") (pin "2") (pinfunction "2_2") (pintype "passive"))
      (node (ref "C7") (pin "2") (pinfunction "2_2") (pintype "passive"))
      (node (ref "C8") (pin "2") (pinfunction "2_2") (pintype "passive"))
      (node (ref "C9") (pin "-") (pinfunction "-_-") (pintype "passive"))
      (node (ref "IC1") (pin "11") (pinfunction "GND_2_11") (pintype "passive"))
      (node (ref "IC1") (pin "32") (pinfunction "GND_4_32") (pintype "passive"))
      (node (ref "IC1") (pin "62") (pinfunction "GND_3_62") (pintype "passive"))
      (node (ref "IC1") (pin "81") (pinfunction "GND_5_81") (pintype "passive"))
      (node (ref "IC1") (pin "99") (pinfunction "GND_99") (pintype "passive"))
      (node (ref "IC2") (pin "2") (pinfunction "VSS_2") (pintype "passive"))
      (node (ref "IC2") (pin "8") (pinfunction "RS_8") (pintype "input"))
      (node (ref "IC3") (pin "9") (pinfunction "VSS_9") (pintype "power_in"))
      (node (ref "IC5") (pin "4") (pinfunction "GND1_4") (pintype "passive"))
      (node (ref "IC8") (pin "3") (pinfunction "GND_3") (pintype "passive"))
      (node (ref "ISP") (pin "6") (pinfunction "S_6") (pintype "passive"))
      (node (ref "I²C") (pin "3") (pinfunction "S_3") (pintype "passive"))
      (node (ref "J1") (pin "3") (pinfunction "3_3") (pintype "passive"))
      (node (ref "J1") (pin "4") (pinfunction "4_4") (pintype "passive"))
      (node (ref "J1") (pin "SHELL") (pinfunction "SHIELD_SHELL") (pintype "passive"))
      (node (ref "J1") (pin "SHELL1") (pinfunction "SHIELD_SHELL1") (pintype "passive"))
      (node (ref "J2") (pin "3") (pinfunction "3_3") (pintype "passive"))
      (node (ref "J2") (pin "4") (pinfunction "4_4") (pintype "passive"))
      (node (ref "J2") (pin "SHELL") (pinfunction "SHIELD_SHELL") (pintype "passive"))
      (node (ref "J2") (pin "SHELL1") (pinfunction "SHIELD_SHELL1") (pintype "passive"))
      (node (ref "OK1") (pin "11") (pinfunction "EMIT_11") (pintype "passive"))
      (node (ref "OK1") (pin "13") (pinfunction "EMIT_13") (pintype "passive"))
      (node (ref "OK1") (pin "15") (pinfunction "EMIT_15") (pintype "passive"))
      (node (ref "OK1") (pin "9") (pinfunction "EMIT_9") (pintype "passive"))
      (node (ref "OK2") (pin "11") (pinfunction "EMIT_11") (pintype "passive"))
      (node (ref "OK2") (pin "13") (pinfunction "EMIT_13") (pintype "passive"))
      (node (ref "OK2") (pin "15") (pinfunction "EMIT_15") (pintype "passive"))
      (node (ref "OK2") (pin "9") (pinfunction "EMIT_9") (pintype "passive"))
      (node (ref "OK3") (pin "11") (pinfunction "EMIT_11") (pintype "passive"))
      (node (ref "OK3") (pin "13") (pinfunction "EMIT_13") (pintype "passive"))
      (node (ref "OK3") (pin "15") (pinfunction "EMIT_15") (pintype "passive"))
      (node (ref "OK3") (pin "9") (pinfunction "EMIT_9") (pintype "passive"))
      (node (ref "OK4") (pin "11") (pinfunction "EMIT_11") (pintype "passive"))
      (node (ref "OK4") (pin "13") (pinfunction "EMIT_13") (pintype "passive"))
      (node (ref "OK4") (pin "15") (pinfunction "EMIT_15") (pintype "passive"))
      (node (ref "OK4") (pin "9") (pinfunction "EMIT_9") (pintype "passive"))
      (node (ref "OK5") (pin "11") (pinfunction "EMIT_11") (pintype "passive"))
      (node (ref "OK5") (pin "13") (pinfunction "EMIT_13") (pintype "passive"))
      (node (ref "OK5") (pin "15") (pinfunction "EMIT_15") (pintype "passive"))
      (node (ref "OK5") (pin "9") (pinfunction "EMIT_9") (pintype "passive"))
      (node (ref "OK6") (pin "11") (pinfunction "EMIT_11") (pintype "passive"))
      (node (ref "OK6") (pin "13") (pinfunction "EMIT_13") (pintype "passive"))
      (node (ref "OK6") (pin "15") (pinfunction "EMIT_15") (pintype "passive"))
      (node (ref "OK6") (pin "9") (pinfunction "EMIT_9") (pintype "passive"))
      (node (ref "OK7") (pin "11") (pinfunction "EMIT_11") (pintype "passive"))
      (node (ref "OK7") (pin "13") (pinfunction "EMIT_13") (pintype "passive"))
      (node (ref "OK7") (pin "15") (pinfunction "EMIT_15") (pintype "passive"))
      (node (ref "OK7") (pin "9") (pinfunction "EMIT_9") (pintype "passive"))
      (node (ref "OK8") (pin "11") (pinfunction "EMIT_11") (pintype "passive"))
      (node (ref "OK8") (pin "13") (pinfunction "EMIT_13") (pintype "passive"))
      (node (ref "OK8") (pin "15") (pinfunction "EMIT_15") (pintype "passive"))
      (node (ref "OK8") (pin "9") (pinfunction "EMIT_9") (pintype "passive"))
      (node (ref "OK9") (pin "3") (pinfunction "EMIT_3") (pintype "passive"))
      (node (ref "R4") (pin "2") (pinfunction "2_2") (pintype "passive"))
      (node (ref "R5") (pin "2") (pinfunction "2_2") (pintype "passive"))
      (node (ref "S1") (pin "1") (pinfunction "1_1") (pintype "passive"))
      (node (ref "S1") (pin "2") (pinfunction "2_2") (pintype "passive"))
      (node (ref "S1") (pin "3") (pinfunction "3_3") (pintype "passive"))
      (node (ref "S1") (pin "4") (pinfunction "4_4") (pintype "passive"))
      (node (ref "U$15") (pin "P$1") (pinfunction "P$1_P$1") (pintype "bidirectional"))
      (node (ref "U$15") (pin "P$2") (pinfunction "P$2_P$2") (pintype "bidirectional"))
      (node (ref "X17") (pin "1") (pinfunction "1_1") (pintype "passive"))
      (node (ref "X5") (pin "1") (pinfunction "1_1") (pintype "passive"))
      (node (ref "X7") (pin "1") (pinfunction "1_1") (pintype "passive"))
    )
    (net (code "49") (name "GND2") (class "Default")
      (node (ref "C43") (pin "2") (pinfunction "2_2") (pintype "passive"))
      (node (ref "C44") (pin "2") (pinfunction "2_2") (pintype "passive"))
      (node (ref "C45") (pin "2") (pinfunction "2_2") (pintype "passive"))
      (node (ref "C47") (pin "2") (pinfunction "2_2") (pintype "passive"))
      (node (ref "GND") (pin "TP") (pinfunction "TP_TP") (pintype "input"))
      (node (ref "IC4") (pin "28") (pinfunction "UGND_28") (pintype "power_in"))
      (node (ref "IC4") (pin "3") (pinfunction "GND_3") (pintype "power_in"))
      (node (ref "IC4") (pin "33") (pinfunction "EXP_33") (pintype "power_in"))
      (node (ref "IC5") (pin "5") (pinfunction "GND2_5") (pintype "passive"))
      (node (ref "X6") (pin "5") (pinfunction "5_5") (pintype "passive"))
    )
    (net (code "50") (name "H0") (class "Default")
      (node (ref "IC1") (pin "12") (pinfunction "(RXD2)_PH0_12") (pintype "bidirectional"))
      (node (ref "T20") (pin "C") (pinfunction "C_C") (pintype "passive"))
    )
    (net (code "51") (name "H1") (class "Default")
      (node (ref "IC1") (pin "13") (pinfunction "(TXD2)_PH1_13") (pintype "bidirectional"))
      (node (ref "T19") (pin "C") (pinfunction "C_C") (pintype "passive"))
    )
    (net (code "52") (name "H2") (class "Default")
      (node (ref "IC1") (pin "14") (pinfunction "(XCK2)_PH2_14") (pintype "bidirectional"))
      (node (ref "T18") (pin "C") (pinfunction "C_C") (pintype "passive"))
    )
    (net (code "53") (name "H3") (class "Default")
      (node (ref "IC1") (pin "15") (pinfunction "(OC4A)_PH3_15") (pintype "bidirectional"))
      (node (ref "T17") (pin "C") (pinfunction "C_C") (pintype "passive"))
    )
    (net (code "54") (name "H4") (class "Default")
      (node (ref "IC1") (pin "16") (pinfunction "(OC4B)_PH4_16") (pintype "bidirectional"))
      (node (ref "OK5") (pin "16") (pinfunction "COL_16") (pintype "passive"))
    )
    (net (code "55") (name "H5") (class "Default")
      (node (ref "IC1") (pin "17") (pinfunction "(OC4C)_PH5_17") (pintype "bidirectional"))
      (node (ref "OK5") (pin "14") (pinfunction "COL_14") (pintype "passive"))
    )
    (net (code "56") (name "H6") (class "Default")
      (node (ref "IC1") (pin "18") (pinfunction "(OC2B)_PH6_18") (pintype "bidirectional"))
      (node (ref "OK5") (pin "12") (pinfunction "COL_12") (pintype "passive"))
    )
    (net (code "57") (name "H7") (class "Default")
      (node (ref "IC1") (pin "27") (pinfunction "(T4)_PH7_27") (pintype "bidirectional"))
      (node (ref "OK5") (pin "10") (pinfunction "COL_10") (pintype "passive"))
    )
    (net (code "58") (name "INT") (class "Default")
      (node (ref "IC1") (pin "45") (pinfunction "(RXD1/INT2)_PD2_45") (pintype "bidirectional"))
      (node (ref "IC3") (pin "12") (pinfunction "~{INT}_12") (pintype "output"))
    )
    (net (code "59") (name "J0") (class "Default")
      (node (ref "IC1") (pin "63") (pinfunction "PJ0_(RXD3/PCINT9)_63") (pintype "bidirectional"))
      (node (ref "T8") (pin "C") (pinfunction "C_C") (pintype "passive"))
    )
    (net (code "60") (name "J1") (class "Default")
      (node (ref "IC1") (pin "64") (pinfunction "PJ1_(TXD3/PCINT10)_64") (pintype "bidirectional"))
      (node (ref "T7") (pin "C") (pinfunction "C_C") (pintype "passive"))
    )
    (net (code "61") (name "J2") (class "Default")
      (node (ref "IC1") (pin "65") (pinfunction "PJ2_(XCK3/PCINT11)_65") (pintype "bidirectional"))
      (node (ref "T6") (pin "C") (pinfunction "C_C") (pintype "passive"))
    )
    (net (code "62") (name "J3") (class "Default")
      (node (ref "IC1") (pin "66") (pinfunction "PJ3_(PCINT12)_66") (pintype "bidirectional"))
      (node (ref "T5") (pin "C") (pinfunction "C_C") (pintype "passive"))
    )
    (net (code "63") (name "J4") (class "Default")
      (node (ref "IC1") (pin "67") (pinfunction "PJ4_(PCINT13)_67") (pintype "bidirectional"))
      (node (ref "OK2") (pin "10") (pinfunction "COL_10") (pintype "passive"))
    )
    (net (code "64") (name "J5") (class "Default")
      (node (ref "IC1") (pin "68") (pinfunction "PJ5_(PCINT14)_68") (pintype "bidirectional"))
      (node (ref "OK2") (pin "12") (pinfunction "COL_12") (pintype "passive"))
    )
    (net (code "65") (name "J6") (class "Default")
      (node (ref "IC1") (pin "69") (pinfunction "PJ6_(PCINT15)_69") (pintype "bidirectional"))
      (node (ref "OK2") (pin "14") (pinfunction "COL_14") (pintype "passive"))
    )
    (net (code "66") (name "J7") (class "Default")
      (node (ref "IC1") (pin "79") (pinfunction "PJ7_79") (pintype "bidirectional"))
      (node (ref "OK2") (pin "16") (pinfunction "COL_16") (pintype "passive"))
    )
    (net (code "67") (name "K0") (class "Default")
      (node (ref "IC1") (pin "89") (pinfunction "PK0_(ADC8/PCINT16)_89") (pintype "bidirectional"))
      (node (ref "T29") (pin "C") (pinfunction "C_C") (pintype "passive"))
    )
    (net (code "68") (name "K1") (class "Default")
      (node (ref "IC1") (pin "88") (pinfunction "PK1_(ADC9/PCINT17)_88") (pintype "bidirectional"))
      (node (ref "T30") (pin "C") (pinfunction "C_C") (pintype "passive"))
    )
    (net (code "69") (name "K2") (class "Default")
      (node (ref "IC1") (pin "87") (pinfunction "PK2_(ADC10/PCINT18)_87") (pintype "bidirectional"))
      (node (ref "T31") (pin "C") (pinfunction "C_C") (pintype "passive"))
    )
    (net (code "70") (name "K3") (class "Default")
      (node (ref "IC1") (pin "86") (pinfunction "PK3_(ADC11/PCINT19)_86") (pintype "bidirectional"))
      (node (ref "T32") (pin "C") (pinfunction "C_C") (pintype "passive"))
    )
    (net (code "71") (name "K4") (class "Default")
      (node (ref "IC1") (pin "85") (pinfunction "PK4_(ADC12/PCINT20)_85") (pintype "bidirectional"))
      (node (ref "OK8") (pin "10") (pinfunction "COL_10") (pintype "passive"))
    )
    (net (code "72") (name "K5") (class "Default")
      (node (ref "IC1") (pin "84") (pinfunction "PK5_(ADC13/PCINT21)_84") (pintype "bidirectional"))
      (node (ref "OK8") (pin "12") (pinfunction "COL_12") (pintype "passive"))
    )
    (net (code "73") (name "K6") (class "Default")
      (node (ref "IC1") (pin "83") (pinfunction "PK6_(ADC14/PCINT22)_83") (pintype "bidirectional"))
      (node (ref "OK8") (pin "14") (pinfunction "COL_14") (pintype "passive"))
    )
    (net (code "74") (name "K7") (class "Default")
      (node (ref "IC1") (pin "82") (pinfunction "PK7_(ADC15/PCINT23)_82") (pintype "bidirectional"))
      (node (ref "OK8") (pin "16") (pinfunction "COL_16") (pintype "passive"))
    )
    (net (code "75") (name "L0") (class "Default")
      (node (ref "IC1") (pin "35") (pinfunction "(ICP4)_PL0_35") (pintype "bidirectional"))
      (node (ref "OK4") (pin "16") (pinfunction "COL_16") (pintype "passive"))
    )
    (net (code "76") (name "L1") (class "Default")
      (node (ref "IC1") (pin "36") (pinfunction "(ICP5)_PL1_36") (pintype "bidirectional"))
      (node (ref "OK4") (pin "14") (pinfunction "COL_14") (pintype "passive"))
    )
    (net (code "77") (name "L2") (class "Default")
      (node (ref "IC1") (pin "37") (pinfunction "(T5)_PL2_37") (pintype "bidirectional"))
      (node (ref "OK4") (pin "12") (pinfunction "COL_12") (pintype "passive"))
    )
    (net (code "78") (name "L3") (class "Default")
      (node (ref "IC1") (pin "38") (pinfunction "(OC5A)_PL3_38") (pintype "bidirectional"))
      (node (ref "OK4") (pin "10") (pinfunction "COL_10") (pintype "passive"))
    )
    (net (code "79") (name "L4") (class "Default")
      (node (ref "IC1") (pin "39") (pinfunction "(OC5B)_PL4_39") (pintype "bidirectional"))
      (node (ref "T16") (pin "C") (pinfunction "C_C") (pintype "passive"))
    )
    (net (code "80") (name "L5") (class "Default")
      (node (ref "IC1") (pin "40") (pinfunction "OC5C)_PL5_40") (pintype "bidirectional"))
      (node (ref "T15") (pin "C") (pinfunction "C_C") (pintype "passive"))
    )
    (net (code "81") (name "L6") (class "Default")
      (node (ref "IC1") (pin "41") (pinfunction "PL6_41") (pintype "bidirectional"))
      (node (ref "T14") (pin "C") (pinfunction "C_C") (pintype "passive"))
    )
    (net (code "82") (name "L7") (class "Default")
      (node (ref "IC1") (pin "42") (pinfunction "PL7_42") (pintype "bidirectional"))
      (node (ref "T13") (pin "C") (pinfunction "C_C") (pintype "passive"))
    )
    (net (code "83") (name "MISO") (class "Default")
      (node (ref "IC1") (pin "22") (pinfunction "(MISO/PCINT3)_PB3_22") (pintype "bidirectional"))
      (node (ref "IC3") (pin "15") (pinfunction "SO_15") (pintype "output"))
      (node (ref "ISP") (pin "1") (pinfunction "S_1") (pintype "passive"))
    )
    (net (code "84") (name "MISO2") (class "Default")
      (node (ref "IC4") (pin "17") (pinfunction "PB3_17") (pintype "bidirectional"))
      (node (ref "MISO") (pin "TP") (pinfunction "TP_TP") (pintype "input"))
    )
    (net (code "85") (name "MOSI") (class "Default")
      (node (ref "IC1") (pin "21") (pinfunction "(MOSI/PCINT2)_PB2_21") (pintype "bidirectional"))
      (node (ref "IC3") (pin "14") (pinfunction "SI_14") (pintype "input"))
      (node (ref "ISP") (pin "4") (pinfunction "S_4") (pintype "passive"))
    )
    (net (code "86") (name "MOSI2") (class "Default")
      (node (ref "IC4") (pin "16") (pinfunction "PB2_16") (pintype "bidirectional"))
      (node (ref "MOSI") (pin "TP") (pinfunction "TP_TP") (pintype "input"))
    )
    (net (code "87") (name "Net-(B1-Pad+)") (class "Default")
      (node (ref "B1") (pin "+") (pinfunction "+_+") (pintype "passive"))
      (node (ref "B1") (pin "-") (pinfunction "-_-") (pintype "passive"))
    )
    (net (code "88") (name "Net-(B1-PadAC1)") (class "Default")
      (node (ref "B1") (pin "AC1") (pinfunction "AC1_AC1") (pintype "passive"))
      (node (ref "R9") (pin "2") (pinfunction "2_2") (pintype "passive"))
      (node (ref "X1") (pin "2") (pinfunction "2_2") (pintype "passive"))
    )
    (net (code "89") (name "Net-(B2-Pad+)") (class "Default")
      (node (ref "B2") (pin "+") (pinfunction "+_+") (pintype "passive"))
      (node (ref "B2") (pin "-") (pinfunction "-_-") (pintype "passive"))
    )
    (net (code "90") (name "Net-(B2-PadAC1)") (class "Default")
      (node (ref "B2") (pin "AC1") (pinfunction "AC1_AC1") (pintype "passive"))
      (node (ref "R10") (pin "2") (pinfunction "2_2") (pintype "passive"))
      (node (ref "X1") (pin "3") (pinfunction "3_3") (pintype "passive"))
    )
    (net (code "91") (name "Net-(B3-Pad+)") (class "Default")
      (node (ref "B3") (pin "+") (pinfunction "+_+") (pintype "passive"))
      (node (ref "B3") (pin "-") (pinfunction "-_-") (pintype "passive"))
    )
    (net (code "92") (name "Net-(B3-PadAC1)") (class "Default")
      (node (ref "B3") (pin "AC1") (pinfunction "AC1_AC1") (pintype "passive"))
      (node (ref "R11") (pin "2") (pinfunction "2_2") (pintype "passive"))
      (node (ref "X1") (pin "4") (pinfunction "4_4") (pintype "passive"))
    )
    (net (code "93") (name "Net-(B4-Pad+)") (class "Default")
      (node (ref "B4") (pin "+") (pinfunction "+_+") (pintype "passive"))
      (node (ref "B4") (pin "-") (pinfunction "-_-") (pintype "passive"))
    )
    (net (code "94") (name "Net-(B4-PadAC1)") (class "Default")
      (node (ref "B4") (pin "AC1") (pinfunction "AC1_AC1") (pintype "passive"))
      (node (ref "R12") (pin "2") (pinfunction "2_2") (pintype "passive"))
      (node (ref "X1") (pin "5") (pinfunction "5_5") (pintype "passive"))
    )
    (net (code "95") (name "Net-(B5-Pad+)") (class "Default")
      (node (ref "B5") (pin "+") (pinfunction "+_+") (pintype "passive"))
      (node (ref "B5") (pin "-") (pinfunction "-_-") (pintype "passive"))
    )
    (net (code "96") (name "Net-(B5-PadAC1)") (class "Default")
      (node (ref "B5") (pin "AC1") (pinfunction "AC1_AC1") (pintype "passive"))
      (node (ref "R13") (pin "2") (pinfunction "2_2") (pintype "passive"))
      (node (ref "X1") (pin "6") (pinfunction "6_6") (pintype "passive"))
    )
    (net (code "97") (name "Net-(B6-Pad+)") (class "Default")
      (node (ref "B6") (pin "+") (pinfunction "+_+") (pintype "passive"))
      (node (ref "B6") (pin "-") (pinfunction "-_-") (pintype "passive"))
    )
    (net (code "98") (name "Net-(B6-PadAC1)") (class "Default")
      (node (ref "B6") (pin "AC1") (pinfunction "AC1_AC1") (pintype "passive"))
      (node (ref "R14") (pin "2") (pinfunction "2_2") (pintype "passive"))
      (node (ref "X1") (pin "7") (pinfunction "7_7") (pintype "passive"))
    )
    (net (code "99") (name "Net-(B7-Pad+)") (class "Default")
      (node (ref "B7") (pin "+") (pinfunction "+_+") (pintype "passive"))
      (node (ref "B7") (pin "-") (pinfunction "-_-") (pintype "passive"))
    )
    (net (code "100") (name "Net-(B7-PadAC1)") (class "Default")
      (node (ref "B7") (pin "AC1") (pinfunction "AC1_AC1") (pintype "passive"))
      (node (ref "R15") (pin "2") (pinfunction "2_2") (pintype "passive"))
      (node (ref "X1") (pin "8") (pinfunction "8_8") (pintype "passive"))
    )
    (net (code "101") (name "Net-(B8-Pad+)") (class "Default")
      (node (ref "B8") (pin "+") (pinfunction "+_+") (pintype "passive"))
      (node (ref "B8") (pin "-") (pinfunction "-_-") (pintype "passive"))
    )
    (net (code "102") (name "Net-(B8-PadAC1)") (class "Default")
      (node (ref "B8") (pin "AC1") (pinfunction "AC1_AC1") (pintype "passive"))
      (node (ref "R16") (pin "2") (pinfunction "2_2") (pintype "passive"))
      (node (ref "X1") (pin "9") (pinfunction "9_9") (pintype "passive"))
    )
    (net (code "103") (name "Net-(B9-Pad+)") (class "Default")
      (node (ref "B9") (pin "+") (pinfunction "+_+") (pintype "passive"))
      (node (ref "B9") (pin "-") (pinfunction "-_-") (pintype "passive"))
    )
    (net (code "104") (name "Net-(B9-PadAC1)") (class "Default")
      (node (ref "B9") (pin "AC1") (pinfunction "AC1_AC1") (pintype "passive"))
      (node (ref "R17") (pin "2") (pinfunction "2_2") (pintype "passive"))
      (node (ref "X2") (pin "2") (pinfunction "2_2") (pintype "passive"))
    )
    (net (code "105") (name "Net-(B10-Pad+)") (class "Default")
      (node (ref "B10") (pin "+") (pinfunction "+_+") (pintype "passive"))
      (node (ref "B10") (pin "-") (pinfunction "-_-") (pintype "passive"))
    )
    (net (code "106") (name "Net-(B10-PadAC1)") (class "Default")
      (node (ref "B10") (pin "AC1") (pinfunction "AC1_AC1") (pintype "passive"))
      (node (ref "R18") (pin "2") (pinfunction "2_2") (pintype "passive"))
      (node (ref "X2") (pin "3") (pinfunction "3_3") (pintype "passive"))
    )
    (net (code "107") (name "Net-(B11-Pad+)") (class "Default")
      (node (ref "B11") (pin "+") (pinfunction "+_+") (pintype "passive"))
      (node (ref "B11") (pin "-") (pinfunction "-_-") (pintype "passive"))
    )
    (net (code "108") (name "Net-(B11-PadAC1)") (class "Default")
      (node (ref "B11") (pin "AC1") (pinfunction "AC1_AC1") (pintype "passive"))
      (node (ref "R19") (pin "2") (pinfunction "2_2") (pintype "passive"))
      (node (ref "X2") (pin "4") (pinfunction "4_4") (pintype "passive"))
    )
    (net (code "109") (name "Net-(B12-Pad+)") (class "Default")
      (node (ref "B12") (pin "+") (pinfunction "+_+") (pintype "passive"))
      (node (ref "B12") (pin "-") (pinfunction "-_-") (pintype "passive"))
    )
    (net (code "110") (name "Net-(B12-PadAC1)") (class "Default")
      (node (ref "B12") (pin "AC1") (pinfunction "AC1_AC1") (pintype "passive"))
      (node (ref "R20") (pin "2") (pinfunction "2_2") (pintype "passive"))
      (node (ref "X2") (pin "5") (pinfunction "5_5") (pintype "passive"))
    )
    (net (code "111") (name "Net-(B13-Pad+)") (class "Default")
      (node (ref "B13") (pin "+") (pinfunction "+_+") (pintype "passive"))
      (node (ref "B13") (pin "-") (pinfunction "-_-") (pintype "passive"))
    )
    (net (code "112") (name "Net-(B13-PadAC1)") (class "Default")
      (node (ref "B13") (pin "AC1") (pinfunction "AC1_AC1") (pintype "passive"))
      (node (ref "R21") (pin "2") (pinfunction "2_2") (pintype "passive"))
      (node (ref "X2") (pin "6") (pinfunction "6_6") (pintype "passive"))
    )
    (net (code "113") (name "Net-(B14-Pad+)") (class "Default")
      (node (ref "B14") (pin "+") (pinfunction "+_+") (pintype "passive"))
      (node (ref "B14") (pin "-") (pinfunction "-_-") (pintype "passive"))
    )
    (net (code "114") (name "Net-(B14-PadAC1)") (class "Default")
      (node (ref "B14") (pin "AC1") (pinfunction "AC1_AC1") (pintype "passive"))
      (node (ref "R22") (pin "2") (pinfunction "2_2") (pintype "passive"))
      (node (ref "X2") (pin "7") (pinfunction "7_7") (pintype "passive"))
    )
    (net (code "115") (name "Net-(B15-Pad+)") (class "Default")
      (node (ref "B15") (pin "+") (pinfunction "+_+") (pintype "passive"))
      (node (ref "B15") (pin "-") (pinfunction "-_-") (pintype "passive"))
    )
    (net (code "116") (name "Net-(B15-PadAC1)") (class "Default")
      (node (ref "B15") (pin "AC1") (pinfunction "AC1_AC1") (pintype "passive"))
      (node (ref "R23") (pin "2") (pinfunction "2_2") (pintype "passive"))
      (node (ref "X2") (pin "8") (pinfunction "8_8") (pintype "passive"))
    )
    (net (code "117") (name "Net-(B16-Pad+)") (class "Default")
      (node (ref "B16") (pin "+") (pinfunction "+_+") (pintype "passive"))
      (node (ref "B16") (pin "-") (pinfunction "-_-") (pintype "passive"))
    )
    (net (code "118") (name "Net-(B16-PadAC1)") (class "Default")
      (node (ref "B16") (pin "AC1") (pinfunction "AC1_AC1") (pintype "passive"))
      (node (ref "R24") (pin "2") (pinfunction "2_2") (pintype "passive"))
      (node (ref "X2") (pin "9") (pinfunction "9_9") (pintype "passive"))
    )
    (net (code "119") (name "Net-(B17-Pad+)") (class "Default")
      (node (ref "B17") (pin "+") (pinfunction "+_+") (pintype "passive"))
      (node (ref "B17") (pin "-") (pinfunction "-_-") (pintype "passive"))
    )
    (net (code "120") (name "Net-(B17-PadAC1)") (class "Default")
      (node (ref "B17") (pin "AC1") (pinfunction "AC1_AC1") (pintype "passive"))
      (node (ref "R25") (pin "2") (pinfunction "2_2") (pintype "passive"))
      (node (ref "X3") (pin "2") (pinfunction "2_2") (pintype "passive"))
    )
    (net (code "121") (name "Net-(B18-Pad+)") (class "Default")
      (node (ref "B18") (pin "+") (pinfunction "+_+") (pintype "passive"))
      (node (ref "B18") (pin "-") (pinfunction "-_-") (pintype "passive"))
    )
    (net (code "122") (name "Net-(B18-PadAC1)") (class "Default")
      (node (ref "B18") (pin "AC1") (pinfunction "AC1_AC1") (pintype "passive"))
      (node (ref "R26") (pin "2") (pinfunction "2_2") (pintype "passive"))
      (node (ref "X3") (pin "3") (pinfunction "3_3") (pintype "passive"))
    )
    (net (code "123") (name "Net-(B19-Pad+)") (class "Default")
      (node (ref "B19") (pin "+") (pinfunction "+_+") (pintype "passive"))
      (node (ref "B19") (pin "-") (pinfunction "-_-") (pintype "passive"))
    )
    (net (code "124") (name "Net-(B19-PadAC1)") (class "Default")
      (node (ref "B19") (pin "AC1") (pinfunction "AC1_AC1") (pintype "passive"))
      (node (ref "R27") (pin "2") (pinfunction "2_2") (pintype "passive"))
      (node (ref "X3") (pin "4") (pinfunction "4_4") (pintype "passive"))
    )
    (net (code "125") (name "Net-(B20-Pad+)") (class "Default")
      (node (ref "B20") (pin "+") (pinfunction "+_+") (pintype "passive"))
      (node (ref "B20") (pin "-") (pinfunction "-_-") (pintype "passive"))
    )
    (net (code "126") (name "Net-(B20-PadAC1)") (class "Default")
      (node (ref "B20") (pin "AC1") (pinfunction "AC1_AC1") (pintype "passive"))
      (node (ref "R28") (pin "2") (pinfunction "2_2") (pintype "passive"))
      (node (ref "X3") (pin "5") (pinfunction "5_5") (pintype "passive"))
    )
    (net (code "127") (name "Net-(B21-Pad+)") (class "Default")
      (node (ref "B21") (pin "+") (pinfunction "+_+") (pintype "passive"))
      (node (ref "B21") (pin "-") (pinfunction "-_-") (pintype "passive"))
    )
    (net (code "128") (name "Net-(B21-PadAC1)") (class "Default")
      (node (ref "B21") (pin "AC1") (pinfunction "AC1_AC1") (pintype "passive"))
      (node (ref "R29") (pin "2") (pinfunction "2_2") (pintype "passive"))
      (node (ref "X3") (pin "6") (pinfunction "6_6") (pintype "passive"))
    )
    (net (code "129") (name "Net-(B22-Pad+)") (class "Default")
      (node (ref "B22") (pin "+") (pinfunction "+_+") (pintype "passive"))
      (node (ref "B22") (pin "-") (pinfunction "-_-") (pintype "passive"))
    )
    (net (code "130") (name "Net-(B22-PadAC1)") (class "Default")
      (node (ref "B22") (pin "AC1") (pinfunction "AC1_AC1") (pintype "passive"))
      (node (ref "R30") (pin "2") (pinfunction "2_2") (pintype "passive"))
      (node (ref "X3") (pin "7") (pinfunction "7_7") (pintype "passive"))
    )
    (net (code "131") (name "Net-(B23-Pad+)") (class "Default")
      (node (ref "B23") (pin "+") (pinfunction "+_+") (pintype "passive"))
      (node (ref "B23") (pin "-") (pinfunction "-_-") (pintype "passive"))
    )
    (net (code "132") (name "Net-(B23-PadAC1)") (class "Default")
      (node (ref "B23") (pin "AC1") (pinfunction "AC1_AC1") (pintype "passive"))
      (node (ref "R31") (pin "2") (pinfunction "2_2") (pintype "passive"))
      (node (ref "X3") (pin "8") (pinfunction "8_8") (pintype "passive"))
    )
    (net (code "133") (name "Net-(B24-Pad+)") (class "Default")
      (node (ref "B24") (pin "+") (pinfunction "+_+") (pintype "passive"))
      (node (ref "B24") (pin "-") (pinfunction "-_-") (pintype "passive"))
    )
    (net (code "134") (name "Net-(B24-PadAC1)") (class "Default")
      (node (ref "B24") (pin "AC1") (pinfunction "AC1_AC1") (pintype "passive"))
      (node (ref "R32") (pin "2") (pinfunction "2_2") (pintype "passive"))
      (node (ref "X3") (pin "9") (pinfunction "9_9") (pintype "passive"))
    )
    (net (code "135") (name "Net-(B25-Pad+)") (class "Default")
      (node (ref "B25") (pin "+") (pinfunction "+_+") (pintype "passive"))
      (node (ref "B25") (pin "-") (pinfunction "-_-") (pintype "passive"))
    )
    (net (code "136") (name "Net-(B25-PadAC1)") (class "Default")
      (node (ref "B25") (pin "AC1") (pinfunction "AC1_AC1") (pintype "passive"))
      (node (ref "R33") (pin "2") (pinfunction "2_2") (pintype "passive"))
      (node (ref "X4") (pin "2") (pinfunction "2_2") (pintype "passive"))
    )
    (net (code "137") (name "Net-(B26-Pad+)") (class "Default")
      (node (ref "B26") (pin "+") (pinfunction "+_+") (pintype "passive"))
      (node (ref "B26") (pin "-") (pinfunction "-_-") (pintype "passive"))
    )
    (net (code "138") (name "Net-(B26-PadAC1)") (class "Default")
      (node (ref "B26") (pin "AC1") (pinfunction "AC1_AC1") (pintype "passive"))
      (node (ref "R34") (pin "2") (pinfunction "2_2") (pintype "passive"))
      (node (ref "X4") (pin "3") (pinfunction "3_3") (pintype "passive"))
    )
    (net (code "139") (name "Net-(B27-Pad+)") (class "Default")
      (node (ref "B27") (pin "+") (pinfunction "+_+") (pintype "passive"))
      (node (ref "B27") (pin "-") (pinfunction "-_-") (pintype "passive"))
    )
    (net (code "140") (name "Net-(B27-PadAC1)") (class "Default")
      (node (ref "B27") (pin "AC1") (pinfunction "AC1_AC1") (pintype "passive"))
      (node (ref "R35") (pin "2") (pinfunction "2_2") (pintype "passive"))
      (node (ref "X4") (pin "4") (pinfunction "4_4") (pintype "passive"))
    )
    (net (code "141") (name "Net-(B28-Pad+)") (class "Default")
      (node (ref "B28") (pin "+") (pinfunction "+_+") (pintype "passive"))
      (node (ref "B28") (pin "-") (pinfunction "-_-") (pintype "passive"))
    )
    (net (code "142") (name "Net-(B28-PadAC1)") (class "Default")
      (node (ref "B28") (pin "AC1") (pinfunction "AC1_AC1") (pintype "passive"))
      (node (ref "R36") (pin "2") (pinfunction "2_2") (pintype "passive"))
      (node (ref "X4") (pin "5") (pinfunction "5_5") (pintype "passive"))
    )
    (net (code "143") (name "Net-(B29-Pad+)") (class "Default")
      (node (ref "B29") (pin "+") (pinfunction "+_+") (pintype "passive"))
      (node (ref "B29") (pin "-") (pinfunction "-_-") (pintype "passive"))
    )
    (net (code "144") (name "Net-(B29-PadAC1)") (class "Default")
      (node (ref "B29") (pin "AC1") (pinfunction "AC1_AC1") (pintype "passive"))
      (node (ref "R37") (pin "2") (pinfunction "2_2") (pintype "passive"))
      (node (ref "X4") (pin "6") (pinfunction "6_6") (pintype "passive"))
    )
    (net (code "145") (name "Net-(B30-Pad+)") (class "Default")
      (node (ref "B30") (pin "+") (pinfunction "+_+") (pintype "passive"))
      (node (ref "B30") (pin "-") (pinfunction "-_-") (pintype "passive"))
    )
    (net (code "146") (name "Net-(B30-PadAC1)") (class "Default")
      (node (ref "B30") (pin "AC1") (pinfunction "AC1_AC1") (pintype "passive"))
      (node (ref "R38") (pin "2") (pinfunction "2_2") (pintype "passive"))
      (node (ref "X4") (pin "7") (pinfunction "7_7") (pintype "passive"))
    )
    (net (code "147") (name "Net-(B31-Pad+)") (class "Default")
      (node (ref "B31") (pin "+") (pinfunction "+_+") (pintype "passive"))
      (node (ref "B31") (pin "-") (pinfunction "-_-") (pintype "passive"))
    )
    (net (code "148") (name "Net-(B31-PadAC1)") (class "Default")
      (node (ref "B31") (pin "AC1") (pinfunction "AC1_AC1") (pintype "passive"))
      (node (ref "R39") (pin "2") (pinfunction "2_2") (pintype "passive"))
      (node (ref "X4") (pin "8") (pinfunction "8_8") (pintype "passive"))
    )
    (net (code "149") (name "Net-(B32-Pad+)") (class "Default")
      (node (ref "B32") (pin "+") (pinfunction "+_+") (pintype "passive"))
      (node (ref "B32") (pin "-") (pinfunction "-_-") (pintype "passive"))
    )
    (net (code "150") (name "Net-(B32-PadAC1)") (class "Default")
      (node (ref "B32") (pin "AC1") (pinfunction "AC1_AC1") (pintype "passive"))
      (node (ref "R40") (pin "2") (pinfunction "2_2") (pintype "passive"))
      (node (ref "X4") (pin "9") (pinfunction "9_9") (pintype "passive"))
    )
    (net (code "151") (name "Net-(IC1-(ICP1)_PD4)") (class "Default")
      (node (ref "IC1") (pin "47") (pinfunction "(ICP1)_PD4_47") (pintype "bidirectional"))
      (node (ref "S1") (pin "8") (pinfunction "8_8") (pintype "passive"))
    )
    (net (code "152") (name "Net-(IC1-(T0)_PD7)") (class "Default")
      (node (ref "IC1") (pin "50") (pinfunction "(T0)_PD7_50") (pintype "bidirectional"))
      (node (ref "S1") (pin "5") (pinfunction "5_5") (pintype "passive"))
    )
    (net (code "153") (name "Net-(IC1-(T1)_PD6)") (class "Default")
      (node (ref "IC1") (pin "49") (pinfunction "(T1)_PD6_49") (pintype "bidirectional"))
      (node (ref "S1") (pin "6") (pinfunction "6_6") (pintype "passive"))
    )
    (net (code "154") (name "Net-(IC1-(XCK1)_PD5)") (class "Default")
      (node (ref "IC1") (pin "48") (pinfunction "(XCK1)_PD5_48") (pintype "bidirectional"))
      (node (ref "S1") (pin "7") (pinfunction "7_7") (pintype "passive"))
    )
    (net (code "155") (name "Net-(IC4-PD0)") (class "Default")
      (node (ref "C44") (pin "1") (pinfunction "1_1") (pintype "passive"))
      (node (ref "IC4") (pin "6") (pinfunction "PD0_6") (pintype "bidirectional"))
      (node (ref "Q3") (pin "3") (pinfunction "2_3") (pintype "passive"))
      (node (ref "R41") (pin "2") (pinfunction "2_2") (pintype "passive"))
    )
    (net (code "156") (name "Net-(IC4-UCAP)") (class "Default")
      (node (ref "C45") (pin "1") (pinfunction "1_1") (pintype "passive"))
      (node (ref "IC4") (pin "27") (pinfunction "UCAP_27") (pintype "output"))
    )
    (net (code "157") (name "Net-(IC4-XTAL1)") (class "Default")
      (node (ref "C43") (pin "1") (pinfunction "1_1") (pintype "passive"))
      (node (ref "IC4") (pin "1") (pinfunction "XTAL1_1") (pintype "input"))
      (node (ref "Q3") (pin "1") (pinfunction "1_1") (pintype "passive"))
      (node (ref "R41") (pin "1") (pinfunction "1_1") (pintype "passive"))
    )
    (net (code "158") (name "Net-(J1-Pad1)") (class "Default")
      (node (ref "J1") (pin "1") (pinfunction "1_1") (pintype "passive"))
      (node (ref "J2") (pin "1") (pinfunction "1_1") (pintype "passive"))
    )
    (net (code "159") (name "Net-(J1-Pad2)") (class "Default")
      (node (ref "J1") (pin "2") (pinfunction "2_2") (pintype "passive"))
      (node (ref "J2") (pin "2") (pinfunction "2_2") (pintype "passive"))
    )
    (net (code "160") (name "Net-(OK1A-A)") (class "Default")
      (node (ref "C14") (pin "1") (pinfunction "1_1") (pintype "passive"))
      (node (ref "OK1") (pin "1") (pinfunction "A_1") (pintype "passive"))
      (node (ref "R12") (pin "1") (pinfunction "1_1") (pintype "passive"))
    )
    (net (code "161") (name "Net-(OK1B-A)") (class "Default")
      (node (ref "C13") (pin "1") (pinfunction "1_1") (pintype "passive"))
      (node (ref "OK1") (pin "3") (pinfunction "A_3") (pintype "passive"))
      (node (ref "R11") (pin "1") (pinfunction "1_1") (pintype "passive"))
    )
    (net (code "162") (name "Net-(OK1C-A)") (class "Default")
      (node (ref "C12") (pin "1") (pinfunction "1_1") (pintype "passive"))
      (node (ref "OK1") (pin "5") (pinfunction "A_5") (pintype "passive"))
      (node (ref "R10") (pin "1") (pinfunction "1_1") (pintype "passive"))
    )
    (net (code "163") (name "Net-(OK1D-A)") (class "Default")
      (node (ref "C11") (pin "1") (pinfunction "1_1") (pintype "passive"))
      (node (ref "OK1") (pin "7") (pinfunction "A_7") (pintype "passive"))
      (node (ref "R9") (pin "1") (pinfunction "1_1") (pintype "passive"))
    )
    (net (code "164") (name "Net-(OK2A-A)") (class "Default")
      (node (ref "C18") (pin "1") (pinfunction "1_1") (pintype "passive"))
      (node (ref "OK2") (pin "1") (pinfunction "A_1") (pintype "passive"))
      (node (ref "R16") (pin "1") (pinfunction "1_1") (pintype "passive"))
    )
    (net (code "165") (name "Net-(OK2B-A)") (class "Default")
      (node (ref "C17") (pin "1") (pinfunction "1_1") (pintype "passive"))
      (node (ref "OK2") (pin "3") (pinfunction "A_3") (pintype "passive"))
      (node (ref "R15") (pin "1") (pinfunction "1_1") (pintype "passive"))
    )
    (net (code "166") (name "Net-(OK2C-A)") (class "Default")
      (node (ref "C16") (pin "1") (pinfunction "1_1") (pintype "passive"))
      (node (ref "OK2") (pin "5") (pinfunction "A_5") (pintype "passive"))
      (node (ref "R14") (pin "1") (pinfunction "1_1") (pintype "passive"))
    )
    (net (code "167") (name "Net-(OK2D-A)") (class "Default")
      (node (ref "C15") (pin "1") (pinfunction "1_1") (pintype "passive"))
      (node (ref "OK2") (pin "7") (pinfunction "A_7") (pintype "passive"))
      (node (ref "R13") (pin "1") (pinfunction "1_1") (pintype "passive"))
    )
    (net (code "168") (name "Net-(OK3A-A)") (class "Default")
      (node (ref "C22") (pin "1") (pinfunction "1_1") (pintype "passive"))
      (node (ref "OK3") (pin "1") (pinfunction "A_1") (pintype "passive"))
      (node (ref "R20") (pin "1") (pinfunction "1_1") (pintype "passive"))
    )
    (net (code "169") (name "Net-(OK3B-A)") (class "Default")
      (node (ref "C21") (pin "1") (pinfunction "1_1") (pintype "passive"))
      (node (ref "OK3") (pin "3") (pinfunction "A_3") (pintype "passive"))
      (node (ref "R19") (pin "1") (pinfunction "1_1") (pintype "passive"))
    )
    (net (code "170") (name "Net-(OK3C-A)") (class "Default")
      (node (ref "C20") (pin "1") (pinfunction "1_1") (pintype "passive"))
      (node (ref "OK3") (pin "5") (pinfunction "A_5") (pintype "passive"))
      (node (ref "R18") (pin "1") (pinfunction "1_1") (pintype "passive"))
    )
    (net (code "171") (name "Net-(OK3D-A)") (class "Default")
      (node (ref "C19") (pin "1") (pinfunction "1_1") (pintype "passive"))
      (node (ref "OK3") (pin "7") (pinfunction "A_7") (pintype "passive"))
      (node (ref "R17") (pin "1") (pinfunction "1_1") (pintype "passive"))
    )
    (net (code "172") (name "Net-(OK4A-A)") (class "Default")
      (node (ref "C26") (pin "1") (pinfunction "1_1") (pintype "passive"))
      (node (ref "OK4") (pin "1") (pinfunction "A_1") (pintype "passive"))
      (node (ref "R24") (pin "1") (pinfunction "1_1") (pintype "passive"))
    )
    (net (code "173") (name "Net-(OK4B-A)") (class "Default")
      (node (ref "C25") (pin "1") (pinfunction "1_1") (pintype "passive"))
      (node (ref "OK4") (pin "3") (pinfunction "A_3") (pintype "passive"))
      (node (ref "R23") (pin "1") (pinfunction "1_1") (pintype "passive"))
    )
    (net (code "174") (name "Net-(OK4C-A)") (class "Default")
      (node (ref "C24") (pin "1") (pinfunction "1_1") (pintype "passive"))
      (node (ref "OK4") (pin "5") (pinfunction "A_5") (pintype "passive"))
      (node (ref "R22") (pin "1") (pinfunction "1_1") (pintype "passive"))
    )
    (net (code "175") (name "Net-(OK4D-A)") (class "Default")
      (node (ref "C23") (pin "1") (pinfunction "1_1") (pintype "passive"))
      (node (ref "OK4") (pin "7") (pinfunction "A_7") (pintype "passive"))
      (node (ref "R21") (pin "1") (pinfunction "1_1") (pintype "passive"))
    )
    (net (code "176") (name "Net-(OK5A-A)") (class "Default")
      (node (ref "C30") (pin "1") (pinfunction "1_1") (pintype "passive"))
      (node (ref "OK5") (pin "1") (pinfunction "A_1") (pintype "passive"))
      (node (ref "R28") (pin "1") (pinfunction "1_1") (pintype "passive"))
    )
    (net (code "177") (name "Net-(OK5B-A)") (class "Default")
      (node (ref "C29") (pin "1") (pinfunction "1_1") (pintype "passive"))
      (node (ref "OK5") (pin "3") (pinfunction "A_3") (pintype "passive"))
      (node (ref "R27") (pin "1") (pinfunction "1_1") (pintype "passive"))
    )
    (net (code "178") (name "Net-(OK5C-A)") (class "Default")
      (node (ref "C28") (pin "1") (pinfunction "1_1") (pintype "passive"))
      (node (ref "OK5") (pin "5") (pinfunction "A_5") (pintype "passive"))
      (node (ref "R26") (pin "1") (pinfunction "1_1") (pintype "passive"))
    )
    (net (code "179") (name "Net-(OK5D-A)") (class "Default")
      (node (ref "C27") (pin "1") (pinfunction "1_1") (pintype "passive"))
      (node (ref "OK5") (pin "7") (pinfunction "A_7") (pintype "passive"))
      (node (ref "R25") (pin "1") (pinfunction "1_1") (pintype "passive"))
    )
    (net (code "180") (name "Net-(OK6A-A)") (class "Default")
      (node (ref "C34") (pin "1") (pinfunction "1_1") (pintype "passive"))
      (node (ref "OK6") (pin "1") (pinfunction "A_1") (pintype "passive"))
      (node (ref "R32") (pin "1") (pinfunction "1_1") (pintype "passive"))
    )
    (net (code "181") (name "Net-(OK6B-A)") (class "Default")
      (node (ref "C33") (pin "1") (pinfunction "1_1") (pintype "passive"))
      (node (ref "OK6") (pin "3") (pinfunction "A_3") (pintype "passive"))
      (node (ref "R31") (pin "1") (pinfunction "1_1") (pintype "passive"))
    )
    (net (code "182") (name "Net-(OK6C-A)") (class "Default")
      (node (ref "C32") (pin "1") (pinfunction "1_1") (pintype "passive"))
      (node (ref "OK6") (pin "5") (pinfunction "A_5") (pintype "passive"))
      (node (ref "R30") (pin "1") (pinfunction "1_1") (pintype "passive"))
    )
    (net (code "183") (name "Net-(OK6D-A)") (class "Default")
      (node (ref "C31") (pin "1") (pinfunction "1_1") (pintype "passive"))
      (node (ref "OK6") (pin "7") (pinfunction "A_7") (pintype "passive"))
      (node (ref "R29") (pin "1") (pinfunction "1_1") (pintype "passive"))
    )
    (net (code "184") (name "Net-(OK7A-A)") (class "Default")
      (node (ref "C38") (pin "1") (pinfunction "1_1") (pintype "passive"))
      (node (ref "OK7") (pin "1") (pinfunction "A_1") (pintype "passive"))
      (node (ref "R36") (pin "1") (pinfunction "1_1") (pintype "passive"))
    )
    (net (code "185") (name "Net-(OK7B-A)") (class "Default")
      (node (ref "C37") (pin "1") (pinfunction "1_1") (pintype "passive"))
      (node (ref "OK7") (pin "3") (pinfunction "A_3") (pintype "passive"))
      (node (ref "R35") (pin "1") (pinfunction "1_1") (pintype "passive"))
    )
    (net (code "186") (name "Net-(OK7C-A)") (class "Default")
      (node (ref "C36") (pin "1") (pinfunction "1_1") (pintype "passive"))
      (node (ref "OK7") (pin "5") (pinfunction "A_5") (pintype "passive"))
      (node (ref "R34") (pin "1") (pinfunction "1_1") (pintype "passive"))
    )
    (net (code "187") (name "Net-(OK7D-A)") (class "Default")
      (node (ref "C35") (pin "1") (pinfunction "1_1") (pintype "passive"))
      (node (ref "OK7") (pin "7") (pinfunction "A_7") (pintype "passive"))
      (node (ref "R33") (pin "1") (pinfunction "1_1") (pintype "passive"))
    )
    (net (code "188") (name "Net-(OK8A-A)") (class "Default")
      (node (ref "C42") (pin "1") (pinfunction "1_1") (pintype "passive"))
      (node (ref "OK8") (pin "1") (pinfunction "A_1") (pintype "passive"))
      (node (ref "R40") (pin "1") (pinfunction "1_1") (pintype "passive"))
    )
    (net (code "189") (name "Net-(OK8B-A)") (class "Default")
      (node (ref "C41") (pin "1") (pinfunction "1_1") (pintype "passive"))
      (node (ref "OK8") (pin "3") (pinfunction "A_3") (pintype "passive"))
      (node (ref "R39") (pin "1") (pinfunction "1_1") (pintype "passive"))
    )
    (net (code "190") (name "Net-(OK8C-A)") (class "Default")
      (node (ref "C40") (pin "1") (pinfunction "1_1") (pintype "passive"))
      (node (ref "OK8") (pin "5") (pinfunction "A_5") (pintype "passive"))
      (node (ref "R38") (pin "1") (pinfunction "1_1") (pintype "passive"))
    )
    (net (code "191") (name "Net-(OK8D-A)") (class "Default")
      (node (ref "C39") (pin "1") (pinfunction "1_1") (pintype "passive"))
      (node (ref "OK8") (pin "7") (pinfunction "A_7") (pintype "passive"))
      (node (ref "R37") (pin "1") (pinfunction "1_1") (pintype "passive"))
    )
    (net (code "192") (name "Net-(OK9-C)") (class "Default")
      (node (ref "OK9") (pin "2") (pinfunction "C_2") (pintype "passive"))
      (node (ref "R46") (pin "1") (pinfunction "1_1") (pintype "passive"))
    )
    (net (code "193") (name "Net-(OK9-COL)") (class "Default")
      (node (ref "C46") (pin "1") (pinfunction "1_1") (pintype "passive"))
      (node (ref "OK9") (pin "4") (pinfunction "COL_4") (pintype "passive"))
      (node (ref "R45") (pin "1") (pinfunction "1_1") (pintype "passive"))
    )
    (net (code "194") (name "Net-(POWER-PadC)") (class "Default")
      (node (ref "POWER") (pin "C") (pinfunction "C_C") (pintype "passive"))
      (node (ref "R4") (pin "1") (pinfunction "1_1") (pintype "passive"))
    )
    (net (code "195") (name "Net-(R3-Pad2)") (class "Default")
      (node (ref "R3") (pin "2") (pinfunction "2_2") (pintype "passive"))
      (node (ref "TERM") (pin "1") (pinfunction "1_1") (pintype "passive"))
    )
    (net (code "196") (name "Net-(R5-Pad1)") (class "Default")
      (node (ref "R5") (pin "1") (pinfunction "1_1") (pintype "passive"))
      (node (ref "STATUS") (pin "C") (pinfunction "C_C") (pintype "passive"))
    )
    (net (code "197") (name "Net-(R42-Pad2)") (class "Default")
      (node (ref "R42") (pin "2") (pinfunction "2_2") (pintype "passive"))
      (node (ref "X6") (pin "2") (pinfunction "2_2") (pintype "passive"))
    )
    (net (code "198") (name "Net-(R43-Pad2)") (class "Default")
      (node (ref "R43") (pin "2") (pinfunction "2_2") (pintype "passive"))
      (node (ref "X6") (pin "3") (pinfunction "3_3") (pintype "passive"))
    )
    (net (code "199") (name "Net-(R47-Pad1)") (class "Default")
      (node (ref "R47") (pin "1") (pinfunction "1_1") (pintype "passive"))
      (node (ref "USBRX") (pin "C") (pinfunction "C_C") (pintype "passive"))
    )
    (net (code "200") (name "Net-(R48-Pad1)") (class "Default")
      (node (ref "R48") (pin "1") (pinfunction "1_1") (pintype "passive"))
      (node (ref "USBTX") (pin "C") (pinfunction "C_C") (pintype "passive"))
    )
    (net (code "201") (name "Net-(RN1-Pad1)") (class "Default")
      (node (ref "RN1") (pin "1") (pinfunction "1_1") (pintype "passive"))
      (node (ref "T1") (pin "A") (pinfunction "A_A") (pintype "passive"))
    )
    (net (code "202") (name "Net-(RN1B-1)") (class "Default")
      (node (ref "RN1") (pin "2") (pinfunction "1_2") (pintype "passive"))
      (node (ref "T2") (pin "A") (pinfunction "A_A") (pintype "passive"))
    )
    (net (code "203") (name "Net-(RN1C-1)") (class "Default")
      (node (ref "RN1") (pin "3") (pinfunction "1_3") (pintype "passive"))
      (node (ref "T3") (pin "A") (pinfunction "A_A") (pintype "passive"))
    )
    (net (code "204") (name "Net-(RN1D-1)") (class "Default")
      (node (ref "RN1") (pin "4") (pinfunction "1_4") (pintype "passive"))
      (node (ref "T4") (pin "A") (pinfunction "A_A") (pintype "passive"))
    )
    (net (code "205") (name "Net-(RN2-Pad1)") (class "Default")
      (node (ref "RN2") (pin "1") (pinfunction "1_1") (pintype "passive"))
      (node (ref "T5") (pin "A") (pinfunction "A_A") (pintype "passive"))
    )
    (net (code "206") (name "Net-(RN2B-1)") (class "Default")
      (node (ref "RN2") (pin "2") (pinfunction "1_2") (pintype "passive"))
      (node (ref "T6") (pin "A") (pinfunction "A_A") (pintype "passive"))
    )
    (net (code "207") (name "Net-(RN2C-1)") (class "Default")
      (node (ref "RN2") (pin "3") (pinfunction "1_3") (pintype "passive"))
      (node (ref "T7") (pin "A") (pinfunction "A_A") (pintype "passive"))
    )
    (net (code "208") (name "Net-(RN2D-1)") (class "Default")
      (node (ref "RN2") (pin "4") (pinfunction "1_4") (pintype "passive"))
      (node (ref "T8") (pin "A") (pinfunction "A_A") (pintype "passive"))
    )
    (net (code "209") (name "Net-(RN3-Pad1)") (class "Default")
      (node (ref "RN3") (pin "1") (pinfunction "1_1") (pintype "passive"))
      (node (ref "T9") (pin "A") (pinfunction "A_A") (pintype "passive"))
    )
    (net (code "210") (name "Net-(RN3B-1)") (class "Default")
      (node (ref "RN3") (pin "2") (pinfunction "1_2") (pintype "passive"))
      (node (ref "T10") (pin "A") (pinfunction "A_A") (pintype "passive"))
    )
    (net (code "211") (name "Net-(RN3C-1)") (class "Default")
      (node (ref "RN3") (pin "3") (pinfunction "1_3") (pintype "passive"))
      (node (ref "T11") (pin "A") (pinfunction "A_A") (pintype "passive"))
    )
    (net (code "212") (name "Net-(RN3D-1)") (class "Default")
      (node (ref "RN3") (pin "4") (pinfunction "1_4") (pintype "passive"))
      (node (ref "T12") (pin "A") (pinfunction "A_A") (pintype "passive"))
    )
    (net (code "213") (name "Net-(RN4-Pad1)") (class "Default")
      (node (ref "RN4") (pin "1") (pinfunction "1_1") (pintype "passive"))
      (node (ref "T13") (pin "A") (pinfunction "A_A") (pintype "passive"))
    )
    (net (code "214") (name "Net-(RN4B-1)") (class "Default")
      (node (ref "RN4") (pin "2") (pinfunction "1_2") (pintype "passive"))
      (node (ref "T14") (pin "A") (pinfunction "A_A") (pintype "passive"))
    )
    (net (code "215") (name "Net-(RN4C-1)") (class "Default")
      (node (ref "RN4") (pin "3") (pinfunction "1_3") (pintype "passive"))
      (node (ref "T15") (pin "A") (pinfunction "A_A") (pintype "passive"))
    )
    (net (code "216") (name "Net-(RN4D-1)") (class "Default")
      (node (ref "RN4") (pin "4") (pinfunction "1_4") (pintype "passive"))
      (node (ref "T16") (pin "A") (pinfunction "A_A") (pintype "passive"))
    )
    (net (code "217") (name "Net-(RN5-Pad1)") (class "Default")
      (node (ref "RN5") (pin "1") (pinfunction "1_1") (pintype "passive"))
      (node (ref "T17") (pin "A") (pinfunction "A_A") (pintype "passive"))
    )
    (net (code "218") (name "Net-(RN5B-1)") (class "Default")
      (node (ref "RN5") (pin "2") (pinfunction "1_2") (pintype "passive"))
      (node (ref "T18") (pin "A") (pinfunction "A_A") (pintype "passive"))
    )
    (net (code "219") (name "Net-(RN5C-1)") (class "Default")
      (node (ref "RN5") (pin "3") (pinfunction "1_3") (pintype "passive"))
      (node (ref "T19") (pin "A") (pinfunction "A_A") (pintype "passive"))
    )
    (net (code "220") (name "Net-(RN5D-1)") (class "Default")
      (node (ref "RN5") (pin "4") (pinfunction "1_4") (pintype "passive"))
      (node (ref "T20") (pin "A") (pinfunction "A_A") (pintype "passive"))
    )
    (net (code "221") (name "Net-(RN6-Pad1)") (class "Default")
      (node (ref "RN6") (pin "1") (pinfunction "1_1") (pintype "passive"))
      (node (ref "T21") (pin "A") (pinfunction "A_A") (pintype "passive"))
    )
    (net (code "222") (name "Net-(RN6B-1)") (class "Default")
      (node (ref "RN6") (pin "2") (pinfunction "1_2") (pintype "passive"))
      (node (ref "T22") (pin "A") (pinfunction "A_A") (pintype "passive"))
    )
    (net (code "223") (name "Net-(RN6C-1)") (class "Default")
      (node (ref "RN6") (pin "3") (pinfunction "1_3") (pintype "passive"))
      (node (ref "T23") (pin "A") (pinfunction "A_A") (pintype "passive"))
    )
    (net (code "224") (name "Net-(RN6D-1)") (class "Default")
      (node (ref "RN6") (pin "4") (pinfunction "1_4") (pintype "passive"))
      (node (ref "T24") (pin "A") (pinfunction "A_A") (pintype "passive"))
    )
    (net (code "225") (name "Net-(RN7-Pad1)") (class "Default")
      (node (ref "RN7") (pin "1") (pinfunction "1_1") (pintype "passive"))
      (node (ref "T25") (pin "A") (pinfunction "A_A") (pintype "passive"))
    )
    (net (code "226") (name "Net-(RN7B-1)") (class "Default")
      (node (ref "RN7") (pin "2") (pinfunction "1_2") (pintype "passive"))
      (node (ref "T26") (pin "A") (pinfunction "A_A") (pintype "passive"))
    )
    (net (code "227") (name "Net-(RN7C-1)") (class "Default")
      (node (ref "RN7") (pin "3") (pinfunction "1_3") (pintype "passive"))
      (node (ref "T27") (pin "A") (pinfunction "A_A") (pintype "passive"))
    )
    (net (code "228") (name "Net-(RN7D-1)") (class "Default")
      (node (ref "RN7") (pin "4") (pinfunction "1_4") (pintype "passive"))
      (node (ref "T28") (pin "A") (pinfunction "A_A") (pintype "passive"))
    )
    (net (code "229") (name "Net-(RN8-Pad1)") (class "Default")
      (node (ref "RN8") (pin "1") (pinfunction "1_1") (pintype "passive"))
      (node (ref "T29") (pin "A") (pinfunction "A_A") (pintype "passive"))
    )
    (net (code "230") (name "Net-(RN8B-1)") (class "Default")
      (node (ref "RN8") (pin "2") (pinfunction "1_2") (pintype "passive"))
      (node (ref "T30") (pin "A") (pinfunction "A_A") (pintype "passive"))
    )
    (net (code "231") (name "Net-(RN8C-1)") (class "Default")
      (node (ref "RN8") (pin "3") (pinfunction "1_3") (pintype "passive"))
      (node (ref "T31") (pin "A") (pinfunction "A_A") (pintype "passive"))
    )
    (net (code "232") (name "Net-(RN8D-1)") (class "Default")
      (node (ref "RN8") (pin "4") (pinfunction "1_4") (pintype "passive"))
      (node (ref "T32") (pin "A") (pinfunction "A_A") (pintype "passive"))
    )
    (net (code "233") (name "OSC1") (class "Default")
      (node (ref "C7") (pin "1") (pinfunction "1_1") (pintype "passive"))
      (node (ref "IC3") (pin "8") (pinfunction "OSC1_8") (pintype "input"))
      (node (ref "Q2") (pin "1") (pinfunction "1_1") (pintype "passive"))
      (node (ref "R2") (pin "1") (pinfunction "1_1") (pintype "passive"))
    )
    (net (code "234") (name "OSC2") (class "Default")
      (node (ref "C8") (pin "1") (pinfunction "1_1") (pintype "passive"))
      (node (ref "IC3") (pin "7") (pinfunction "OSC2_7") (pintype "output"))
      (node (ref "Q2") (pin "3") (pinfunction "2_3") (pintype "passive"))
      (node (ref "R2") (pin "2") (pinfunction "2_2") (pintype "passive"))
    )
    (net (code "235") (name "RESET") (class "Default")
      (node (ref "C46") (pin "2") (pinfunction "2_2") (pintype "passive"))
      (node (ref "IC1") (pin "30") (pinfunction "~{RESET}_30") (pintype "input"))
      (node (ref "IC3") (pin "17") (pinfunction "~{RESET}_17") (pintype "input"))
      (node (ref "ISP") (pin "5") (pinfunction "S_5") (pintype "passive"))
      (node (ref "R8") (pin "1") (pinfunction "1_1") (pintype "passive"))
      (node (ref "U$15") (pin "P$3") (pinfunction "P$3_P$3") (pintype "bidirectional"))
      (node (ref "U$15") (pin "P$4") (pinfunction "P$4_P$4") (pintype "bidirectional"))
    )
    (net (code "236") (name "RESET2") (class "Default")
      (node (ref "IC4") (pin "24") (pinfunction "PC1//~{RESET}_24") (pintype "bidirectional"))
      (node (ref "R44") (pin "2") (pinfunction "2_2") (pintype "passive"))
      (node (ref "RS") (pin "TP") (pinfunction "TP_TP") (pintype "input"))
    )
    (net (code "237") (name "RXCAN") (class "Default")
      (node (ref "IC2") (pin "4") (pinfunction "RXD_4") (pintype "output"))
      (node (ref "IC3") (pin "2") (pinfunction "RXCAN_2") (pintype "input"))
    )
    (net (code "238") (name "RXD") (class "Default")
      (node (ref "IC1") (pin "2") (pinfunction "(RXD0/PCINT8)_PE0_2") (pintype "bidirectional"))
      (node (ref "IC5") (pin "2") (pinfunction "VOA_2") (pintype "output"))
    )
    (net (code "239") (name "RXDUSB") (class "Default")
      (node (ref "IC4") (pin "8") (pinfunction "PD2_8") (pintype "bidirectional"))
      (node (ref "IC5") (pin "6") (pinfunction "VOB_6") (pintype "output"))
    )
    (net (code "240") (name "RXLED") (class "Default")
      (node (ref "IC4") (pin "10") (pinfunction "PD4_10") (pintype "bidirectional"))
      (node (ref "R47") (pin "2") (pinfunction "2_2") (pintype "passive"))
    )
    (net (code "241") (name "SCK") (class "Default")
      (node (ref "IC1") (pin "20") (pinfunction "(SCK/PCINT1)_PB1_20") (pintype "bidirectional"))
      (node (ref "IC3") (pin "13") (pinfunction "SCK_13") (pintype "input"))
      (node (ref "ISP") (pin "3") (pinfunction "S_3") (pintype "passive"))
    )
    (net (code "242") (name "SCK2") (class "Default")
      (node (ref "IC4") (pin "15") (pinfunction "PB1_15") (pintype "bidirectional"))
      (node (ref "SCK") (pin "TP") (pinfunction "TP_TP") (pintype "input"))
    )
    (net (code "243") (name "SCL") (class "Default")
      (node (ref "IC1") (pin "43") (pinfunction "(SCL/INT0)_PD0_43") (pintype "bidirectional"))
      (node (ref "I²C") (pin "2") (pinfunction "S_2") (pintype "passive"))
      (node (ref "R6") (pin "1") (pinfunction "1_1") (pintype "passive"))
    )
    (net (code "244") (name "SDA") (class "Default")
      (node (ref "IC1") (pin "44") (pinfunction "(SDA/INT1)_PD1_44") (pintype "bidirectional"))
      (node (ref "I²C") (pin "1") (pinfunction "S_1") (pintype "passive"))
      (node (ref "R7") (pin "1") (pinfunction "1_1") (pintype "passive"))
    )
    (net (code "245") (name "STATUS") (class "Default")
      (node (ref "IC1") (pin "46") (pinfunction "(TXD1/INT3)_PD3_46") (pintype "bidirectional"))
      (node (ref "STATUS") (pin "A") (pinfunction "A_A") (pintype "passive"))
    )
    (net (code "246") (name "TXCAN") (class "Default")
      (node (ref "IC2") (pin "1") (pinfunction "TXD_1") (pintype "input"))
      (node (ref "IC3") (pin "1") (pinfunction "TXCAN_1") (pintype "output"))
    )
    (net (code "247") (name "TXD") (class "Default")
      (node (ref "IC1") (pin "3") (pinfunction "(TXD0)_PE1_3") (pintype "bidirectional"))
      (node (ref "IC5") (pin "3") (pinfunction "VIB_3") (pintype "input"))
    )
    (net (code "248") (name "TXDUSB") (class "Default")
      (node (ref "IC4") (pin "9") (pinfunction "PD3_9") (pintype "bidirectional"))
      (node (ref "IC5") (pin "7") (pinfunction "VIA_7") (pintype "input"))
    )
    (net (code "249") (name "TXLED") (class "Default")
      (node (ref "IC4") (pin "11") (pinfunction "PD5_11") (pintype "bidirectional"))
      (node (ref "R48") (pin "2") (pinfunction "2_2") (pintype "passive"))
    )
    (net (code "250") (name "VCC") (class "Default")
      (node (ref "C1") (pin "1") (pinfunction "1_1") (pintype "passive"))
      (node (ref "C10") (pin "1") (pinfunction "1_1") (pintype "passive"))
      (node (ref "C2") (pin "1") (pinfunction "1_1") (pintype "passive"))
      (node (ref "C3") (pin "1") (pinfunction "1_1") (pintype "passive"))
      (node (ref "C6") (pin "1") (pinfunction "1_1") (pintype "passive"))
      (node (ref "IC1") (pin "10") (pinfunction "VCC_3_10") (pintype "power_in"))
      (node (ref "IC1") (pin "100") (pinfunction "AVCC_100") (pintype "power_in"))
      (node (ref "IC1") (pin "31") (pinfunction "VCC_2_31") (pintype "power_in"))
      (node (ref "IC1") (pin "61") (pinfunction "VCC_4_61") (pintype "power_in"))
      (node (ref "IC1") (pin "80") (pinfunction "VCC_80") (pintype "power_in"))
      (node (ref "IC2") (pin "3") (pinfunction "VDD_3") (pintype "power_in"))
      (node (ref "IC2") (pin "5") (pinfunction "VREF_5") (pintype "output"))
      (node (ref "IC3") (pin "18") (pinfunction "VDD_18") (pintype "power_in"))
      (node (ref "IC5") (pin "1") (pinfunction "VDD1_1") (pintype "power_in"))
      (node (ref "IC8") (pin "2") (pinfunction "VO_2") (pintype "passive"))
      (node (ref "ISP") (pin "2") (pinfunction "S_2") (pintype "passive"))
      (node (ref "POWER") (pin "A") (pinfunction "A_A") (pintype "passive"))
      (node (ref "R45") (pin "2") (pinfunction "2_2") (pintype "passive"))
      (node (ref "R6") (pin "2") (pinfunction "2_2") (pintype "passive"))
      (node (ref "R7") (pin "2") (pinfunction "2_2") (pintype "passive"))
      (node (ref "R8") (pin "2") (pinfunction "2_2") (pintype "passive"))
      (node (ref "RN1") (pin "5") (pinfunction "2_5") (pintype "passive"))
      (node (ref "RN1") (pin "6") (pinfunction "2_6") (pintype "passive"))
      (node (ref "RN1") (pin "7") (pinfunction "2_7") (pintype "passive"))
      (node (ref "RN1") (pin "8") (pinfunction "2_8") (pintype "passive"))
      (node (ref "RN2") (pin "5") (pinfunction "2_5") (pintype "passive"))
      (node (ref "RN2") (pin "6") (pinfunction "2_6") (pintype "passive"))
      (node (ref "RN2") (pin "7") (pinfunction "2_7") (pintype "passive"))
      (node (ref "RN2") (pin "8") (pinfunction "2_8") (pintype "passive"))
      (node (ref "RN3") (pin "5") (pinfunction "2_5") (pintype "passive"))
      (node (ref "RN3") (pin "6") (pinfunction "2_6") (pintype "passive"))
      (node (ref "RN3") (pin "7") (pinfunction "2_7") (pintype "passive"))
      (node (ref "RN3") (pin "8") (pinfunction "2_8") (pintype "passive"))
      (node (ref "RN4") (pin "5") (pinfunction "2_5") (pintype "passive"))
      (node (ref "RN4") (pin "6") (pinfunction "2_6") (pintype "passive"))
      (node (ref "RN4") (pin "7") (pinfunction "2_7") (pintype "passive"))
      (node (ref "RN4") (pin "8") (pinfunction "2_8") (pintype "passive"))
      (node (ref "RN5") (pin "5") (pinfunction "2_5") (pintype "passive"))
      (node (ref "RN5") (pin "6") (pinfunction "2_6") (pintype "passive"))
      (node (ref "RN5") (pin "7") (pinfunction "2_7") (pintype "passive"))
      (node (ref "RN5") (pin "8") (pinfunction "2_8") (pintype "passive"))
      (node (ref "RN6") (pin "5") (pinfunction "2_5") (pintype "passive"))
      (node (ref "RN6") (pin "6") (pinfunction "2_6") (pintype "passive"))
      (node (ref "RN6") (pin "7") (pinfunction "2_7") (pintype "passive"))
      (node (ref "RN6") (pin "8") (pinfunction "2_8") (pintype "passive"))
      (node (ref "RN7") (pin "5") (pinfunction "2_5") (pintype "passive"))
      (node (ref "RN7") (pin "6") (pinfunction "2_6") (pintype "passive"))
      (node (ref "RN7") (pin "7") (pinfunction "2_7") (pintype "passive"))
      (node (ref "RN7") (pin "8") (pinfunction "2_8") (pintype "passive"))
      (node (ref "RN8") (pin "5") (pinfunction "2_5") (pintype "passive"))
      (node (ref "RN8") (pin "6") (pinfunction "2_6") (pintype "passive"))
      (node (ref "RN8") (pin "7") (pinfunction "2_7") (pintype "passive"))
      (node (ref "RN8") (pin "8") (pinfunction "2_8") (pintype "passive"))
    )
    (net (code "251") (name "VCC2") (class "Default")
      (node (ref "C47") (pin "1") (pinfunction "1_1") (pintype "passive"))
      (node (ref "IC4") (pin "31") (pinfunction "UVCC_31") (pintype "power_in"))
      (node (ref "IC4") (pin "32") (pinfunction "AVCC_32") (pintype "power_in"))
      (node (ref "IC4") (pin "4") (pinfunction "VCC_4") (pintype "power_in"))
      (node (ref "IC5") (pin "8") (pinfunction "VDD2_8") (pintype "power_in"))
      (node (ref "OK9") (pin "1") (pinfunction "A_1") (pintype "passive"))
      (node (ref "R44") (pin "1") (pinfunction "1_1") (pintype "passive"))
      (node (ref "USBRX") (pin "A") (pinfunction "A_A") (pintype "passive"))
      (node (ref "USBTX") (pin "A") (pinfunction "A_A") (pintype "passive"))
      (node (ref "VCC") (pin "TP") (pinfunction "TP_TP") (pintype "input"))
      (node (ref "X6") (pin "1") (pinfunction "1_1") (pintype "passive"))
    )
    (net (code "252") (name "XTAL1") (class "Default")
      (node (ref "C4") (pin "1") (pinfunction "1_1") (pintype "passive"))
      (node (ref "IC1") (pin "34") (pinfunction "XTAL1_34") (pintype "input"))
      (node (ref "Q1") (pin "1") (pinfunction "1_1") (pintype "passive"))
      (node (ref "R1") (pin "1") (pinfunction "1_1") (pintype "passive"))
    )
    (net (code "253") (name "XTAL2") (class "Default")
      (node (ref "C5") (pin "1") (pinfunction "1_1") (pintype "passive"))
      (node (ref "IC1") (pin "33") (pinfunction "XTAL2_33") (pintype "output"))
      (node (ref "Q1") (pin "3") (pinfunction "2_3") (pintype "passive"))
      (node (ref "R1") (pin "2") (pinfunction "2_2") (pintype "passive"))
    )
    (net (code "254") (name "unconnected-(H1-MOUNT-PadB3,2)") (class "Default")
      (node (ref "H1") (pin "B3,2") (pinfunction "MOUNT_B3,2") (pintype "passive"))
    )
    (net (code "255") (name "unconnected-(H2-MOUNT-PadB3,2)") (class "Default")
      (node (ref "H2") (pin "B3,2") (pinfunction "MOUNT_B3,2") (pintype "passive"))
    )
    (net (code "256") (name "unconnected-(H3-MOUNT-PadB3,2)") (class "Default")
      (node (ref "H3") (pin "B3,2") (pinfunction "MOUNT_B3,2") (pintype "passive"))
    )
    (net (code "257") (name "unconnected-(H4-MOUNT-PadB3,2)") (class "Default")
      (node (ref "H4") (pin "B3,2") (pinfunction "MOUNT_B3,2") (pintype "passive"))
    )
    (net (code "258") (name "unconnected-(H5-MOUNT-PadB3,2)") (class "Default")
      (node (ref "H5") (pin "B3,2") (pinfunction "MOUNT_B3,2") (pintype "passive"))
    )
    (net (code "259") (name "unconnected-(H6-MOUNT-PadB3,2)") (class "Default")
      (node (ref "H6") (pin "B3,2") (pinfunction "MOUNT_B3,2") (pintype "passive"))
    )
    (net (code "260") (name "unconnected-(IC1-(OC0B)_PG5-Pad1)") (class "Default")
      (node (ref "IC1") (pin "1") (pinfunction "(OC0B)_PG5_1") (pintype "bidirectional"))
    )
    (net (code "261") (name "unconnected-(IC1-(OC1A{slash}PCINT5)_PB5-Pad24)") (class "Default")
      (node (ref "IC1") (pin "24") (pinfunction "(OC1A/PCINT5)_PB5_24") (pintype "bidirectional"))
    )
    (net (code "262") (name "unconnected-(IC1-(OC2A{slash}PCINT4)_PB4-Pad23)") (class "Default")
      (node (ref "IC1") (pin "23") (pinfunction "(OC2A/PCINT4)_PB4_23") (pintype "bidirectional"))
    )
    (net (code "263") (name "unconnected-(IC1-(TOSC1)_PG4-Pad29)") (class "Default")
      (node (ref "IC1") (pin "29") (pinfunction "(TOSC1)_PG4_29") (pintype "bidirectional"))
    )
    (net (code "264") (name "unconnected-(IC1-(TOSC2)_PG3-Pad28)") (class "Default")
      (node (ref "IC1") (pin "28") (pinfunction "(TOSC2)_PG3_28") (pintype "bidirectional"))
    )
    (net (code "265") (name "unconnected-(IC1-AREF-Pad98)") (class "Default")
      (node (ref "IC1") (pin "98") (pinfunction "AREF_98") (pintype "input"))
    )
    (net (code "266") (name "unconnected-(IC1-PG0_(~{WR})-Pad51)") (class "Default")
      (node (ref "IC1") (pin "51") (pinfunction "PG0_(~{WR})_51") (pintype "bidirectional"))
    )
    (net (code "267") (name "unconnected-(IC1-PG1_(~{RD})-Pad52)") (class "Default")
      (node (ref "IC1") (pin "52") (pinfunction "PG1_(~{RD})_52") (pintype "bidirectional"))
    )
    (net (code "268") (name "unconnected-(IC1-PG2_(ALE)-Pad70)") (class "Default")
      (node (ref "IC1") (pin "70") (pinfunction "PG2_(ALE)_70") (pintype "bidirectional"))
    )
    (net (code "269") (name "unconnected-(IC3-CLKOUT{slash}SOF-Pad3)") (class "Default")
      (node (ref "IC3") (pin "3") (pinfunction "CLKOUT/SOF_3") (pintype "output"))
    )
    (net (code "270") (name "unconnected-(IC3-~{RX0BF}-Pad11)") (class "Default")
      (node (ref "IC3") (pin "11") (pinfunction "~{RX0BF}_11") (pintype "output"))
    )
    (net (code "271") (name "unconnected-(IC3-~{RX1BF}-Pad10)") (class "Default")
      (node (ref "IC3") (pin "10") (pinfunction "~{RX1BF}_10") (pintype "output"))
    )
    (net (code "272") (name "unconnected-(IC3-~{TX0RTS}-Pad4)") (class "Default")
      (node (ref "IC3") (pin "4") (pinfunction "~{TX0RTS}_4") (pintype "input"))
    )
    (net (code "273") (name "unconnected-(IC3-~{TX1RTS}-Pad5)") (class "Default")
      (node (ref "IC3") (pin "5") (pinfunction "~{TX1RTS}_5") (pintype "input"))
    )
    (net (code "274") (name "unconnected-(IC3-~{TX2RTS}-Pad6)") (class "Default")
      (node (ref "IC3") (pin "6") (pinfunction "~{TX2RTS}_6") (pintype "input"))
    )
    (net (code "275") (name "unconnected-(IC4-PB0-Pad14)") (class "Default")
      (node (ref "IC4") (pin "14") (pinfunction "PB0_14") (pintype "bidirectional"))
    )
    (net (code "276") (name "unconnected-(IC4-PB4-Pad18)") (class "Default")
      (node (ref "IC4") (pin "18") (pinfunction "PB4_18") (pintype "bidirectional"))
    )
    (net (code "277") (name "unconnected-(IC4-PB5-Pad19)") (class "Default")
      (node (ref "IC4") (pin "19") (pinfunction "PB5_19") (pintype "bidirectional"))
    )
    (net (code "278") (name "unconnected-(IC4-PB6-Pad20)") (class "Default")
      (node (ref "IC4") (pin "20") (pinfunction "PB6_20") (pintype "bidirectional"))
    )
    (net (code "279") (name "unconnected-(IC4-PB7-Pad21)") (class "Default")
      (node (ref "IC4") (pin "21") (pinfunction "PB7_21") (pintype "bidirectional"))
    )
    (net (code "280") (name "unconnected-(IC4-PC0-Pad2)") (class "Default")
      (node (ref "IC4") (pin "2") (pinfunction "PC0_2") (pintype "bidirectional"))
    )
    (net (code "281") (name "unconnected-(IC4-PC2-Pad5)") (class "Default")
      (node (ref "IC4") (pin "5") (pinfunction "PC2_5") (pintype "bidirectional"))
    )
    (net (code "282") (name "unconnected-(IC4-PC4-Pad26)") (class "Default")
      (node (ref "IC4") (pin "26") (pinfunction "PC4_26") (pintype "bidirectional"))
    )
    (net (code "283") (name "unconnected-(IC4-PC5-Pad25)") (class "Default")
      (node (ref "IC4") (pin "25") (pinfunction "PC5_25") (pintype "bidirectional"))
    )
    (net (code "284") (name "unconnected-(IC4-PC6-Pad23)") (class "Default")
      (node (ref "IC4") (pin "23") (pinfunction "PC6_23") (pintype "bidirectional"))
    )
    (net (code "285") (name "unconnected-(IC4-PC7-Pad22)") (class "Default")
      (node (ref "IC4") (pin "22") (pinfunction "PC7_22") (pintype "bidirectional"))
    )
    (net (code "286") (name "unconnected-(IC4-PD1-Pad7)") (class "Default")
      (node (ref "IC4") (pin "7") (pinfunction "PD1_7") (pintype "bidirectional"))
    )
    (net (code "287") (name "unconnected-(IC4-PD6-Pad12)") (class "Default")
      (node (ref "IC4") (pin "12") (pinfunction "PD6_12") (pintype "bidirectional"))
    )
    (net (code "288") (name "unconnected-(X6-Pad4)") (class "Default")
      (node (ref "X6") (pin "4") (pinfunction "4_4") (pintype "passive"))
    )
  )
)
